# Power.net
KiCad netlist of a schematic drawn in Altium Designer
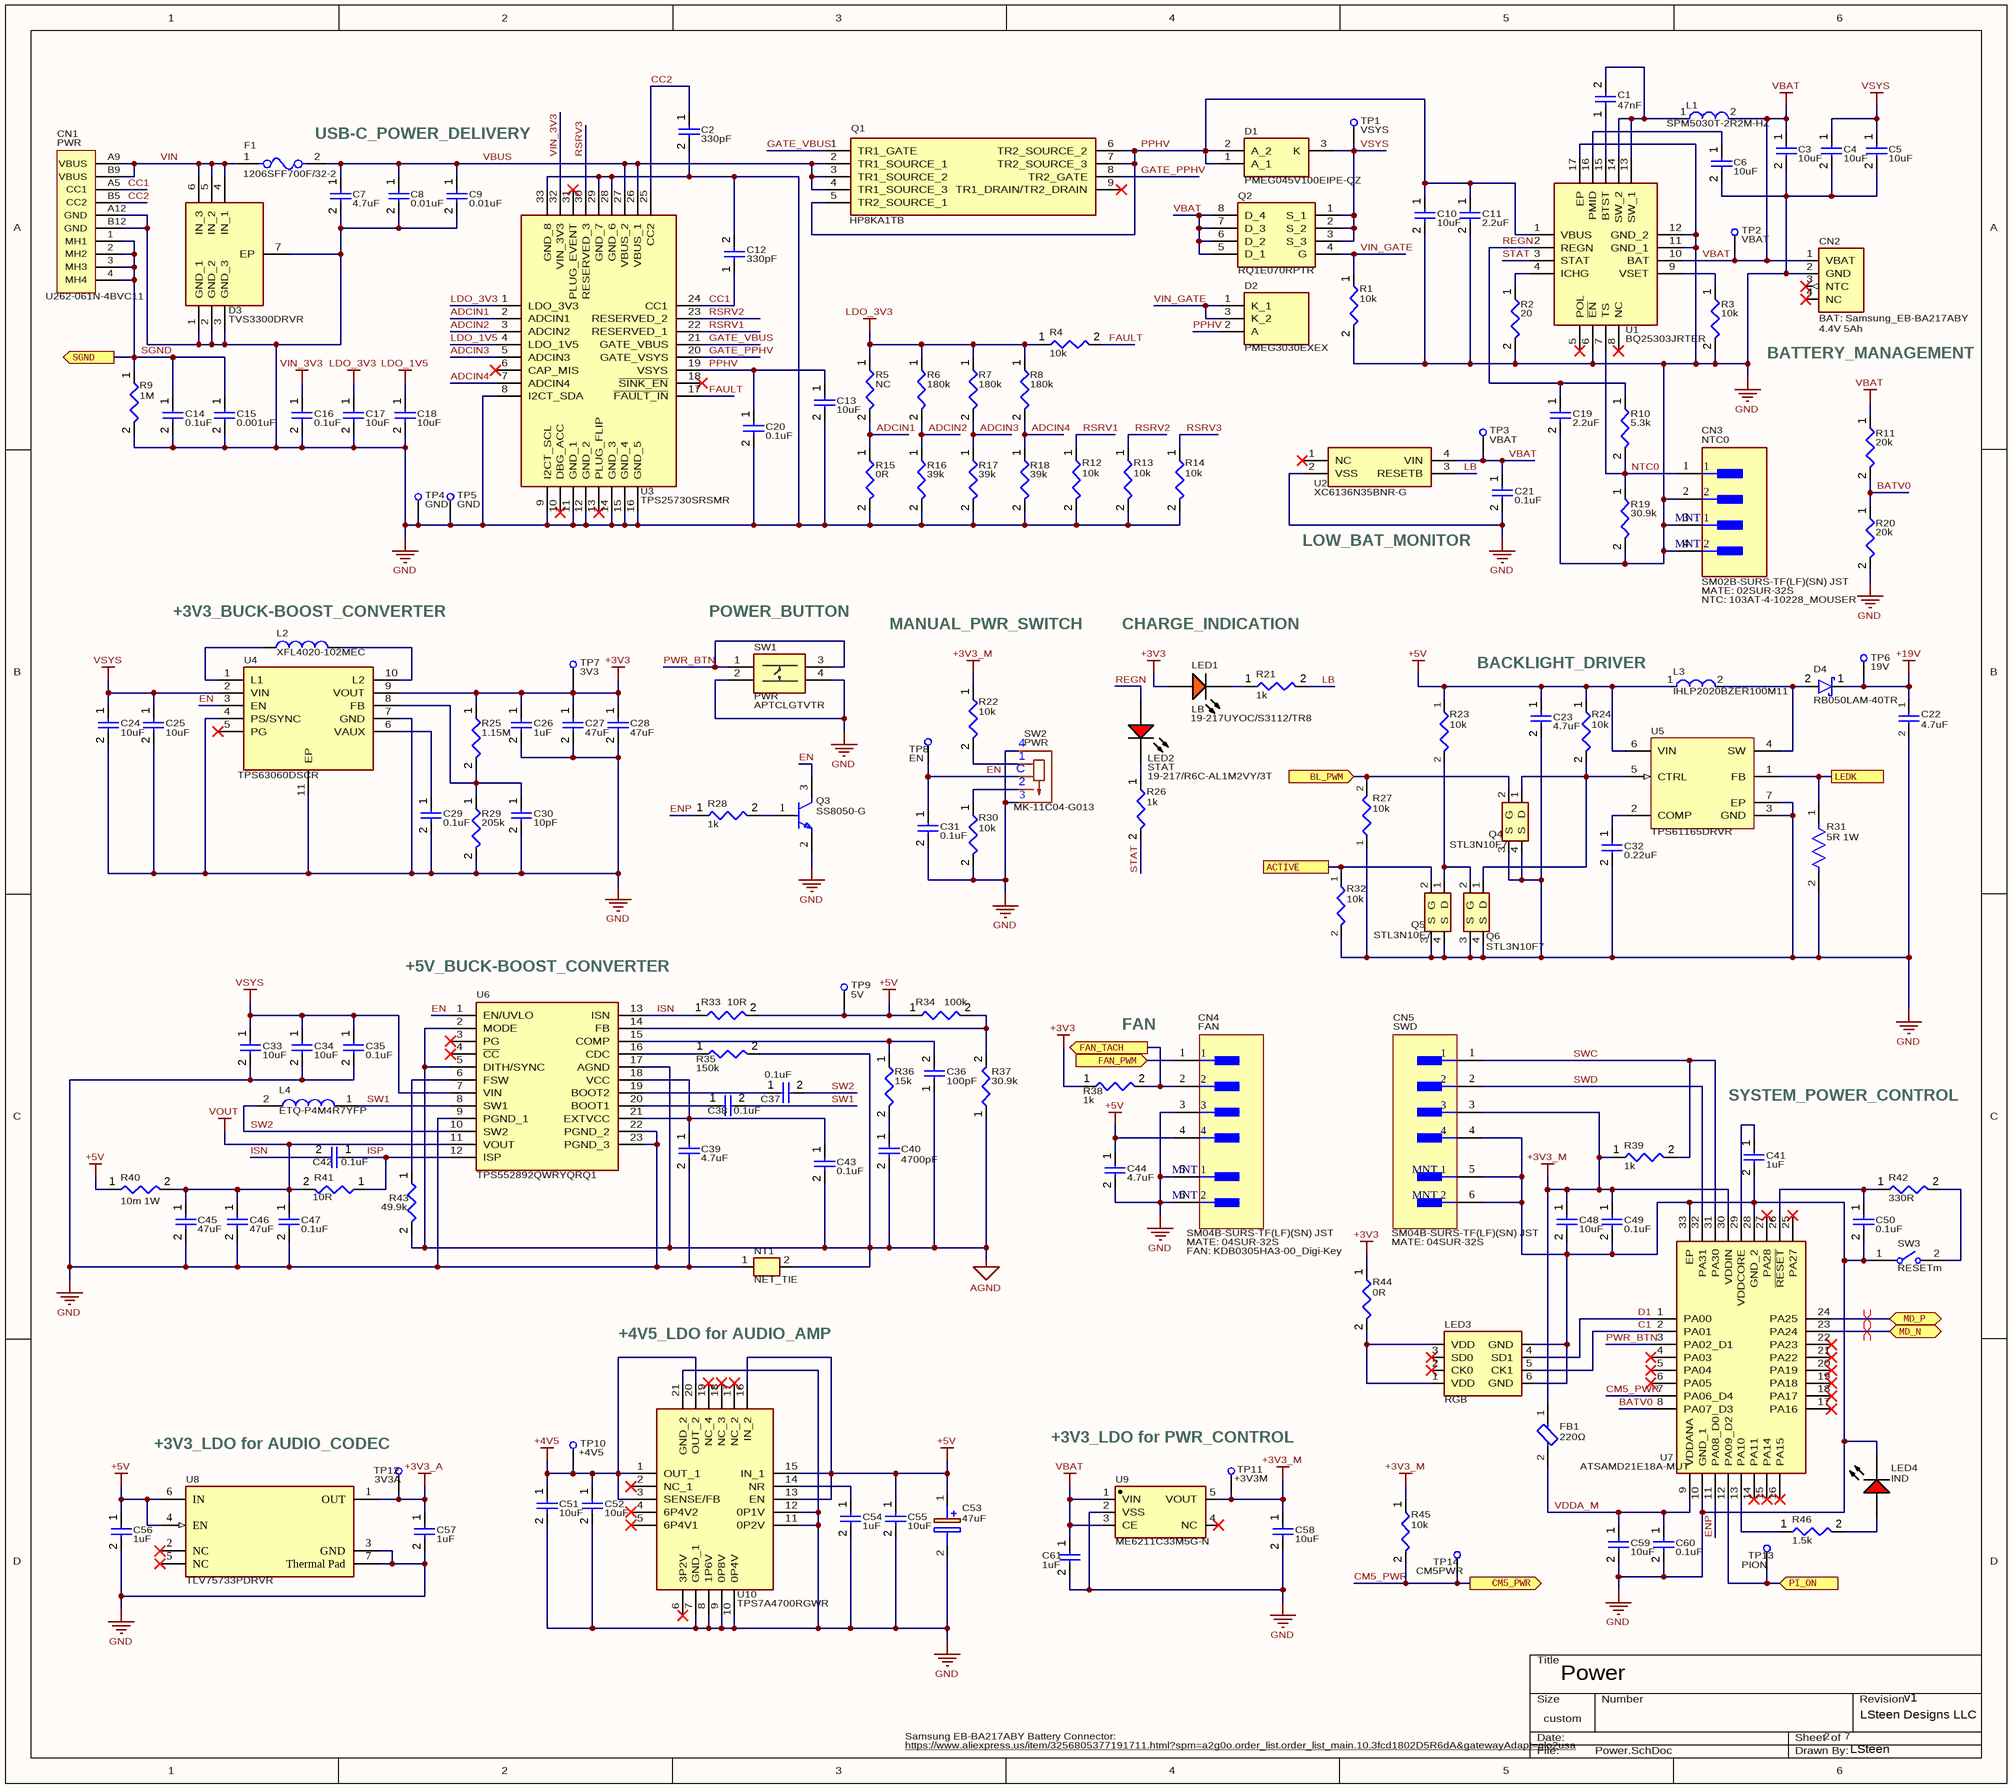
[diagram p0: Power.SchDoc]

(export (version "E")
  (design (tool "Eeschema 10.0.6"))
  (components
    (comp (ref "C1")
      (value "47nF")
      (footprint "CAPC1005X56X25LL10T15")
      (description "Chip Capacitor, 47 nF, +/- 5%, 16 V, 0402 (1005 Metric)")
      (fields (field (name "TOLERANCE") "5%"))
      (libsource (lib "Colorado Technical University") (part "CAP-NP-2"))
    )
    (comp (ref "C2")
      (value "330pF")
      (footprint "CAPC1005X56X25LL10T15")
      (description "Chip Capacitor, 330pF, +/- 5%, 16 V, 0402 (1005 Metric)")
      (fields (field (name "TOLERANCE") "5%"))
      (libsource (lib "Colorado Technical University") (part "CAP-NP-2"))
    )
    (comp (ref "C3")
      (value "10uF")
      (footprint "CAPC0805(2012)145_L")
      (description "Chip Capacitor, 10µF +/-20%, 25V, 0805, Thickness 1.45 mm")
      (fields (field (name "TOLERANCE") "10%"))
      (libsource (lib "Colorado Technical University") (part "CAP-NP-2"))
    )
    (comp (ref "C4")
      (value "10uF")
      (footprint "CAPC0805(2012)145_L")
      (description "Chip Capacitor, 10µF +/-20%, 25V, 0805, Thickness 1.45 mm")
      (fields (field (name "TOLERANCE") "10%"))
      (libsource (lib "Colorado Technical University") (part "CAP-NP-2"))
    )
    (comp (ref "C5")
      (value "10uF")
      (footprint "CAPC0805(2012)145_L")
      (description "Chip Capacitor, 10µF +/-20%, 25V, 0805, Thickness 1.45 mm")
      (fields (field (name "TOLERANCE") "10%"))
      (libsource (lib "Colorado Technical University") (part "CAP-NP-2"))
    )
    (comp (ref "C6")
      (value "10uF")
      (footprint "CAPC0805(2012)145_L")
      (description "Chip Capacitor, 10µF +/-20%, 25V, 0805, Thickness 1.45 mm")
      (fields (field (name "TOLERANCE") "10%"))
      (libsource (lib "Colorado Technical University") (part "CAP-NP-2"))
    )
    (comp (ref "C7")
      (value "4.7uF")
      (footprint "CAPC0603(1608)100_L")
      (description "Chip Capacitor, 4.7uF +/-20%, 10V, 0603, Thickness 1 mm")
      (fields (field (name "TOLERANCE") "10%"))
      (libsource (lib "Colorado Technical University") (part "CAP-NP-2"))
    )
    (comp (ref "C8")
      (value "0.01uF")
      (footprint "CAPC1005X56X25LL10T15")
      (description "Chip Capacitor, 0.01 uF, +/- 5%, 16 V, 0402 (1005 Metric)")
      (fields (field (name "TOLERANCE") "5%"))
      (libsource (lib "Colorado Technical University") (part "CAP-NP-2"))
    )
    (comp (ref "C9")
      (value "0.01uF")
      (footprint "CAPC1005X56X25LL10T15")
      (description "Chip Capacitor, 0.01 uF, +/- 5%, 16 V, 0402 (1005 Metric)")
      (fields (field (name "TOLERANCE") "5%"))
      (libsource (lib "Colorado Technical University") (part "CAP-NP-2"))
    )
    (comp (ref "C10")
      (value "10uF")
      (footprint "CAPC0805(2012)145_L")
      (description "Chip Capacitor, 10µF +/-20%, 25V, 0805, Thickness 1.45 mm")
      (fields (field (name "TOLERANCE") "10%"))
      (libsource (lib "Colorado Technical University") (part "CAP-NP-2"))
    )
    (comp (ref "C11")
      (value "2.2uF")
      (footprint "CAPC0603(1608)100_L")
      (description "Chip Capacitor, 2.2uF +/-20%, 10V, 0603, Thickness 1 mm")
      (fields (field (name "TOLERANCE") "10%"))
      (libsource (lib "Colorado Technical University") (part "CAP-NP-2"))
    )
    (comp (ref "C12")
      (value "330pF")
      (footprint "CAPC1005X56X25LL10T15")
      (description "Chip Capacitor, 330pF, +/- 5%, 16 V, 0402 (1005 Metric)")
      (fields (field (name "TOLERANCE") "5%"))
      (libsource (lib "Colorado Technical University") (part "CAP-NP-2"))
    )
    (comp (ref "C13")
      (value "10uF")
      (footprint "CAPC0603(1608)100_L")
      (description "Chip Capacitor, 10uF +/-20%, 10V, 0603, Thickness 1 mm")
      (fields (field (name "TOLERANCE") "10%"))
      (libsource (lib "Colorado Technical University") (part "CAP-NP-2"))
    )
    (comp (ref "C14")
      (value "0.1uF")
      (footprint "CAPC1005X56X25LL10T15")
      (description "Chip Capacitor, 0.1 uF, +/- 5%, 16 V, 0402 (1005 Metric)")
      (fields (field (name "TOLERANCE") "5%"))
      (libsource (lib "Colorado Technical University") (part "CAP-NP-2"))
    )
    (comp (ref "C15")
      (value "0.001uF")
      (footprint "CAPC1005X56X25LL10T15")
      (description "Chip Capacitor, 0.1 uF, +/- 5%, 16 V, 0402 (1005 Metric)")
      (fields (field (name "TOLERANCE") "5%"))
      (libsource (lib "Colorado Technical University") (part "CAP-NP-2"))
    )
    (comp (ref "C16")
      (value "0.1uF")
      (footprint "CAPC1005X56X25LL10T15")
      (description "Chip Capacitor, 0.1 uF, +/- 5%, 16 V, 0402 (1005 Metric)")
      (fields (field (name "TOLERANCE") "5%"))
      (libsource (lib "Colorado Technical University") (part "CAP-NP-2"))
    )
    (comp (ref "C17")
      (value "10uF")
      (footprint "CAPC0603(1608)100_L")
      (description "Chip Capacitor, 10uF +/-20%, 10V, 0603, Thickness 1 mm")
      (fields (field (name "TOLERANCE") "10%"))
      (libsource (lib "Colorado Technical University") (part "CAP-NP-2"))
    )
    (comp (ref "C18")
      (value "10uF")
      (footprint "CAPC0603(1608)100_L")
      (description "Chip Capacitor, 10uF +/-20%, 10V, 0603, Thickness 1 mm")
      (fields (field (name "TOLERANCE") "10%"))
      (libsource (lib "Colorado Technical University") (part "CAP-NP-2"))
    )
    (comp (ref "C19")
      (value "2.2uF")
      (footprint "CAPC1005X56X25LL10T15")
      (description "Chip Capacitor, 2.2uF uF, +/- 5%, 16 V, 0402 (1005 Metric)")
      (fields (field (name "TOLERANCE") "5%"))
      (libsource (lib "Colorado Technical University") (part "CAP-NP-2"))
    )
    (comp (ref "C20")
      (value "0.1uF")
      (footprint "CAPC1005X56X25LL10T15")
      (description "Chip Capacitor, 0.1 uF, +/- 5%, 16 V, 0402 (1005 Metric)")
      (fields (field (name "TOLERANCE") "5%"))
      (libsource (lib "Colorado Technical University") (part "CAP-NP-2"))
    )
    (comp (ref "C21")
      (value "0.1uF")
      (footprint "CAPC1005X56X25LL10T15")
      (description "Chip Capacitor, 0.1 uF, +/- 5%, 16 V, 0402 (1005 Metric)")
      (fields (field (name "TOLERANCE") "5%"))
      (libsource (lib "Colorado Technical University") (part "CAP-NP-2"))
    )
    (comp (ref "C22")
      (value "4.7uF")
      (footprint "SamacSys:CAPC2012X140N")
      (description "C0805")
      (libsource (lib "SamacSys") (part "C0805"))
    )
    (comp (ref "C23")
      (value "4.7uF")
      (footprint "CAPC0805(2012)145_L")
      (description "Chip Capacitor, 4.7µF +/-20%, 25V, 0805, Thickness 1.45 mm")
      (fields (field (name "TOLERANCE") "10%"))
      (libsource (lib "Colorado Technical University") (part "CAP-NP-2"))
    )
    (comp (ref "C24")
      (value "10uF")
      (footprint "CAPC0603(1608)100_L")
      (description "Chip Capacitor, 10uF +/-20%, 10V, 0603, Thickness 1 mm")
      (fields (field (name "TOLERANCE") "10%"))
      (libsource (lib "Colorado Technical University") (part "CAP-NP-2"))
    )
    (comp (ref "C25")
      (value "10uF")
      (footprint "CAPC0603(1608)100_L")
      (description "Chip Capacitor, 10uF +/-20%, 10V, 0603, Thickness 1 mm")
      (fields (field (name "TOLERANCE") "10%"))
      (libsource (lib "Colorado Technical University") (part "CAP-NP-2"))
    )
    (comp (ref "C26")
      (value "1uF")
      (footprint "CAPC1005X56X25LL10T15")
      (description "Chip Capacitor, 1 uF, +/- 5%, 16 V, 0402 (1005 Metric)")
      (fields (field (name "TOLERANCE") "5%"))
      (libsource (lib "Colorado Technical University") (part "CAP-NP-2"))
    )
    (comp (ref "C27")
      (value "47uF")
      (footprint "CAPC0805(2012)145_L")
      (description "Chip Capacitor, 47µF +/-20%, 25V, 0805, Thickness 1.45 mm")
      (fields (field (name "TOLERANCE") "10%"))
      (libsource (lib "Colorado Technical University") (part "CAP-NP-2"))
    )
    (comp (ref "C28")
      (value "47uF")
      (footprint "CAPC0805(2012)145_L")
      (description "Chip Capacitor, 47µF +/-20%, 25V, 0805, Thickness 1.45 mm")
      (fields (field (name "TOLERANCE") "10%"))
      (libsource (lib "Colorado Technical University") (part "CAP-NP-2"))
    )
    (comp (ref "C29")
      (value "0.1uF")
      (footprint "CAPC1005X56X25LL10T15")
      (description "Chip Capacitor, 0.1 uF, +/- 5%, 16 V, 0402 (1005 Metric)")
      (fields (field (name "TOLERANCE") "5%"))
      (libsource (lib "Colorado Technical University") (part "CAP-NP-2"))
    )
    (comp (ref "C30")
      (value "10pF")
      (footprint "CAPC1005X56X25LL10T15")
      (description "Chip Capacitor, 10 pF, +/- 5%, 16 V, 0402 (1005 Metric)")
      (fields (field (name "TOLERANCE") "5%"))
      (libsource (lib "Colorado Technical University") (part "CAP-NP-2"))
    )
    (comp (ref "C31")
      (value "0.1uF")
      (footprint "CAPC1005X56X25LL10T15")
      (description "Chip Capacitor, 0.1 uF, +/- 5%, 16 V, 0402 (1005 Metric)")
      (fields (field (name "TOLERANCE") "5%"))
      (libsource (lib "Colorado Technical University") (part "CAP-NP-2"))
    )
    (comp (ref "C32")
      (value "0.22uF")
      (footprint "CAPC1005X56X25LL10T15")
      (description "Chip Capacitor, 0.22 uF, +/- 5%, 16 V, 0402 (1005 Metric)")
      (fields (field (name "TOLERANCE") "5%"))
      (libsource (lib "Colorado Technical University") (part "CAP-NP-2"))
    )
    (comp (ref "C33")
      (value "10uF")
      (footprint "CAPC0805(2012)145_L")
      (description "Chip Capacitor, 10µF +/-20%, 25V, 0805, Thickness 1.45 mm")
      (fields (field (name "TOLERANCE") "10%"))
      (libsource (lib "Colorado Technical University") (part "CAP-NP-2"))
    )
    (comp (ref "C34")
      (value "10uF")
      (footprint "CAPC0805(2012)145_L")
      (description "Chip Capacitor, 10µF +/-20%, 25V, 0805, Thickness 1.45 mm")
      (fields (field (name "TOLERANCE") "10%"))
      (libsource (lib "Colorado Technical University") (part "CAP-NP-2"))
    )
    (comp (ref "C35")
      (value "0.1uF")
      (footprint "CAPC1005X56X25LL10T15")
      (description "Chip Capacitor, 0.1 uF, +/- 5%, 16 V, 0402 (1005 Metric)")
      (fields (field (name "TOLERANCE") "5%"))
      (libsource (lib "Colorado Technical University") (part "CAP-NP-2"))
    )
    (comp (ref "C36")
      (value "100pF")
      (footprint "CAPC1005X56X25LL10T15")
      (description "Chip Capacitor, 100 pF, +/- 5%, 16 V, 0402 (1005 Metric)")
      (fields (field (name "TOLERANCE") "5%"))
      (libsource (lib "Colorado Technical University") (part "CAP-NP-2"))
    )
    (comp (ref "C37")
      (value "0.1uF")
      (footprint "CAPC1005X56X25LL10T15")
      (description "Chip Capacitor, 0.1 uF, +/- 5%, 16 V, 0402 (1005 Metric)")
      (fields (field (name "TOLERANCE") "5%"))
      (libsource (lib "Colorado Technical University") (part "CAP-NP-2"))
    )
    (comp (ref "C38")
      (value "0.1uF")
      (footprint "CAPC1005X56X25LL10T15")
      (description "Chip Capacitor, 0.1 uF, +/- 5%, 16 V, 0402 (1005 Metric)")
      (fields (field (name "TOLERANCE") "5%"))
      (libsource (lib "Colorado Technical University") (part "CAP-NP-2"))
    )
    (comp (ref "C39")
      (value "4.7uF")
      (footprint "CAPC0603(1608)100_L")
      (description "Chip Capacitor, 4.7µF +/-20%, 10V, 0603, Thickness 1 mm")
      (fields (field (name "TOLERANCE") "10%"))
      (libsource (lib "Colorado Technical University") (part "CAP-NP-2"))
    )
    (comp (ref "C40")
      (value "4700pF")
      (footprint "CAPC1005X56X25LL10T15")
      (description "Chip Capacitor, 4700 pF, +/- 5%, 16 V, 0402 (1005 Metric)")
      (fields (field (name "TOLERANCE") "5%"))
      (libsource (lib "Colorado Technical University") (part "CAP-NP-2"))
    )
    (comp (ref "C41")
      (value "1uF")
      (footprint "CAPC1005X56X25LL10T15")
      (description "Chip Capacitor, 1 uF, +/- 5%, 16 V, 0402 (1005 Metric)")
      (fields (field (name "TOLERANCE") "5%"))
      (libsource (lib "Colorado Technical University") (part "CAP-NP-2"))
    )
    (comp (ref "C42")
      (value "0.1uF")
      (footprint "CAPC1005X56X25LL10T15")
      (description "Chip Capacitor, 0.1 uF, +/- 5%, 16 V, 0402 (1005 Metric)")
      (fields (field (name "TOLERANCE") "5%"))
      (libsource (lib "Colorado Technical University") (part "CAP-NP-2"))
    )
    (comp (ref "C43")
      (value "0.1uF")
      (footprint "CAPC1005X56X25LL10T15")
      (description "Chip Capacitor, 0.1 uF, +/- 5%, 16 V, 0402 (1005 Metric)")
      (fields (field (name "TOLERANCE") "5%"))
      (libsource (lib "Colorado Technical University") (part "CAP-NP-2"))
    )
    (comp (ref "C44")
      (value "4.7uF")
      (footprint "CAPC0805(2012)145_L")
      (description "Chip Capacitor, 4.7µF +/-20%, 25V, 0805, Thickness 1.45 mm")
      (fields (field (name "TOLERANCE") "10%"))
      (libsource (lib "Colorado Technical University") (part "CAP-NP-2"))
    )
    (comp (ref "C45")
      (value "47uF")
      (footprint "CAPC0805(2012)145_L")
      (description "Chip Capacitor, 47µF +/-40%, 6.3V, 0805, Thickness 1.45 mm")
      (fields (field (name "TOLERANCE") "10%"))
      (libsource (lib "Colorado Technical University") (part "CAP-NP-2"))
    )
    (comp (ref "C46")
      (value "47uF")
      (footprint "CAPC0805(2012)145_L")
      (description "Chip Capacitor, 47µF +/-40%, 6.3V, 0805, Thickness 1.45 mm")
      (fields (field (name "TOLERANCE") "10%"))
      (libsource (lib "Colorado Technical University") (part "CAP-NP-2"))
    )
    (comp (ref "C47")
      (value "0.1uF")
      (footprint "CAPC1005X56X25LL10T15")
      (description "Chip Capacitor, 0.1 uF, +/- 5%, 16 V, 0402 (1005 Metric)")
      (fields (field (name "TOLERANCE") "5%"))
      (libsource (lib "Colorado Technical University") (part "CAP-NP-2"))
    )
    (comp (ref "C48")
      (value "10uF")
      (footprint "CAPC0603(1608)100_L")
      (description "Chip Capacitor, 10uF +/-20%, 10V, 0603, Thickness 1 mm")
      (fields (field (name "TOLERANCE") "10%"))
      (libsource (lib "Colorado Technical University") (part "CAP-NP-2"))
    )
    (comp (ref "C49")
      (value "0.1uF")
      (footprint "CAPC1005X56X25LL10T15")
      (description "Chip Capacitor, 0.1 uF, +/- 5%, 16 V, 0402 (1005 Metric)")
      (fields (field (name "TOLERANCE") "5%"))
      (libsource (lib "Colorado Technical University") (part "CAP-NP-2"))
    )
    (comp (ref "C50")
      (value "0.1uF")
      (footprint "CAPC1005X56X25LL10T15")
      (description "Chip Capacitor, 0.1 uF, +/- 5%, 16 V, 0402 (1005 Metric)")
      (fields (field (name "TOLERANCE") "5%"))
      (libsource (lib "Colorado Technical University") (part "CAP-NP-2"))
    )
    (comp (ref "C51")
      (value "10uF")
      (footprint "CAPC0805(2012)145_L")
      (description "Chip Capacitor, 10µF +/-20%, 25V, 0805, Thickness 1.45 mm")
      (fields (field (name "TOLERANCE") "10%"))
      (libsource (lib "Colorado Technical University") (part "CAP-NP-2"))
    )
    (comp (ref "C52")
      (value "10uF")
      (footprint "CAPC0805(2012)145_L")
      (description "Chip Capacitor, 10µF +/-20%, 25V, 0805, Thickness 1.45 mm")
      (fields (field (name "TOLERANCE") "10%"))
      (libsource (lib "Colorado Technical University") (part "CAP-NP-2"))
    )
    (comp (ref "C53")
      (value "47uF")
      (footprint "SamacSys:CAPPM2014X140N")
      (description "Tantalum TLJR476M010R3200")
      (fields
        (field (name "MANUFACTURER_PART_NUMBER") "TLJR476M010R3200")
        (field (name "MOUSER PART NUMBER") "581-TLJR476M10R3200")
      )
      (libsource (lib "SamacSys") (part "TLJR476M010R3200"))
    )
    (comp (ref "C54")
      (value "1uF")
      (footprint "CAPC0603(1608)100_L")
      (description "Chip Capacitor, 1uF +/-20%, 10V, 0603, Thickness 1 mm")
      (fields (field (name "TOLERANCE") "10%"))
      (libsource (lib "Colorado Technical University") (part "CAP-NP-2"))
    )
    (comp (ref "C55")
      (value "10uF")
      (footprint "CAPC0805(2012)145_L")
      (description "Chip Capacitor, 10µF +/-20%, 25V, 0805, Thickness 1.45 mm")
      (fields (field (name "TOLERANCE") "10%"))
      (libsource (lib "Colorado Technical University") (part "CAP-NP-2"))
    )
    (comp (ref "C56")
      (value "1uF")
      (footprint "CAPC0603(1608)100_L")
      (description "Chip Capacitor, 1uF +/-20%, 10V, 0603, Thickness 1 mm")
      (fields (field (name "TOLERANCE") "10%"))
      (libsource (lib "Colorado Technical University") (part "CAP-NP-2"))
    )
    (comp (ref "C57")
      (value "1uF")
      (footprint "CAPC0603(1608)100_L")
      (description "Chip Capacitor, 1uF +/-20%, 10V, 0603, Thickness 1 mm")
      (fields (field (name "TOLERANCE") "10%"))
      (libsource (lib "Colorado Technical University") (part "CAP-NP-2"))
    )
    (comp (ref "C58")
      (value "10uF")
      (footprint "CAPC0603(1608)100_L")
      (description "Chip Capacitor, 10uF +/-20%, 10V, 0603, Thickness 1 mm")
      (fields (field (name "TOLERANCE") "10%"))
      (libsource (lib "Colorado Technical University") (part "CAP-NP-2"))
    )
    (comp (ref "C59")
      (value "10uF")
      (footprint "CAPC0603(1608)100_L")
      (description "Chip Capacitor, 10uF +/-20%, 10V, 0603, Thickness 1 mm")
      (fields (field (name "TOLERANCE") "10%"))
      (libsource (lib "Colorado Technical University") (part "CAP-NP-2"))
    )
    (comp (ref "C60")
      (value "0.1uF")
      (footprint "CAPC1005X56X25LL10T15")
      (description "Chip Capacitor, 0.1 uF, +/- 5%, 16 V, 0402 (1005 Metric)")
      (fields (field (name "TOLERANCE") "5%"))
      (libsource (lib "Colorado Technical University") (part "CAP-NP-2"))
    )
    (comp (ref "C61")
      (value "1uF")
      (footprint "CAPC0603(1608)100_L")
      (description "Chip Capacitor, 1uF +/-20%, 10V, 0603, Thickness 1 mm")
      (fields (field (name "TOLERANCE") "10%"))
      (libsource (lib "Colorado Technical University") (part "CAP-NP-2"))
    )
    (comp (ref "CN1")
      (value "PWR")
      (footprint "USB-SMD_U262-061N-4BVC11")
      (description "USB-C Connector")
      (fields
        (field (name "MANUFACTURER_PART_NUMBER") "U262-061N-4BVC11")
        (field (name "LCSC PART NUMBER") "C2764612")
      )
      (libsource (lib "Schlib1") (part "U262-061N-4BVC11"))
    )
    (comp (ref "CN2")
      (value "BAT")
      (footprint "BAT_SS_EB-BA217ABY_BRD")
      (description "Samsung battery connector")
      (libsource (lib "Schlib1") (part "BAT_SS_EB-BA217ABY_BRD"))
    )
    (comp (ref "CN3")
      (value "NTC0")
      (footprint "FP-SM02B-SURS-TF_LF_SN-MFG")
      (description "LCSC_CONN HEADER SMD R/A 2POS 0.8MM")
      (libsource (lib "Altium Content Vault") (part "6ebc6fc72a9fd5a6899c7600f385cff"))
    )
    (comp (ref "CN4")
      (value "FAN")
      (footprint "FP-SM04B-SURS-TF_LF_SN-MFG")
      (description "CONN HEADER SMD R/A 4POS 0.8MM")
      (libsource (lib "Altium Content Vault") (part "3b6f738a5616415d78381ad43816e4a"))
    )
    (comp (ref "CN5")
      (value "SWD")
      (footprint "FP-SM04B-SURS-TF_LF_SN-MFG")
      (description "CONN HEADER SMD R/A 4POS 0.8MM")
      (libsource (lib "") (part "3b6f738a5616415d78381ad43816e4a_1"))
    )
    (comp (ref "D1")
      (value "PMEG045V100EIPE-QZ")
      (footprint "SamacSys:PMEG045V100EIPEQZ")
      (description "Schottky Diode")
      (fields (field (name "MOUSER PART NUMBER") "771-MEG045V100EIPEQZ"))
      (libsource (lib "SamacSys") (part "PMEG045V100EIPE-QZ"))
    )
    (comp (ref "D2")
      (value "PMEG3030EXEX")
      (footprint "SamacSys:PMEG4010EXEX")
      (description "Schottky Diode")
      (libsource (lib "SamacSys") (part "PMEG3030EXEX"))
    )
    (comp (ref "D3")
      (value "TVS3300DRVR")
      (footprint "SamacSys:SON65P200X200X80-7N")
      (description "Integrated Circuit")
      (fields (field (name "MOUSER PART NUMBER") "595-TVS3300DRVR"))
      (libsource (lib "SamacSys") (part "TVS3300DRVR"))
    )
    (comp (ref "D4")
      (value "RB050LAM-40TR")
      (footprint "SamacSys:SODFL4725X105N")
      (description "Schottky Diode")
      (fields (field (name "MOUSER PART NUMBER") "755-RB050LAM-40TR"))
      (libsource (lib "SamacSys") (part "RB050LAM-40TR"))
    )
    (comp (ref "F1")
      (value "1206SFF700F/32-2")
      (footprint "FP-1206SFF-MFG")
      (description "FUSE BOARD MOUNT 7A 24VDC 1206")
      (fields
        (field (name "OCTOPART") "https://octopart.com/1206sff700f%2F32-2-littelfuse-74214425")
        (field (name "MANUFACTURER") "Littelfuse")
      )
      (libsource (lib "Altium Content Vault") (part "5bcf9b9f640e542cf0359d10258e979"))
    )
    (comp (ref "FB1")
      (value "220Ω")
      (footprint "FP-BLM18-0_15-t0_5-IPC_B")
      (description "Chip Ferrite Bead, 0603, 220Ω @ 100MHz, 25%, 0.04Ω, 2.5A")
      (libsource (lib "Altium Content Vault") (part "5f30dd21d616792df468990f7003faa"))
    )
    (comp (ref "L1")
      (value "SPM5030T-2R2M-HZ")
      (footprint "FP-SPM5030-MFG")
      (description "FIXED IND 2.2UH 8.5A 21.23 MOHM")
      (fields (field (name "TOLERANCE") "20%"))
      (libsource (lib "Altium Content Vault") (part "725321dda6339637d4d059423bc1c3c"))
    )
    (comp (ref "L2")
      (value "XFL4020-102MEC")
      (footprint "COIL-XFL4020_V")
      (description "Shielded Power Inductor, 1 uH, 64 MHz, -40 to 125 degC, 2-Pin SMD, RoHS, Tape and Reel")
      (fields (field (name "MANUFACTURER") "Coilcraft") (field (name "TOLERANCE") "20%"))
      (libsource (lib "Altium Content Vault") (part "IND-2"))
    )
    (comp (ref "L3")
      (value "IHLP2020BZER100M11")
      (footprint "FP-IHLP-2020BZ-FP_1_905x2-MFG")
      (description "Fixed Inductors Commercial Low DCR Series 10uH 2.2A 182.8mΩ 20%")
      (fields (field (name "TOLERANCE") "20%"))
      (libsource (lib "Altium Content Vault") (part "725321dda6339637d4d059423bc1c3c"))
    )
    (comp (ref "L4")
      (value "ETQ-P4M4R7YFP")
      (footprint "SamacSys:ETQP3M_4M_YFP")
      (description "Inductor")
      (fields (field (name "MOUSER PART NUMBER") "667-ETQ-P4M4R7YFP"))
      (libsource (lib "*") (part "ETQ-P4M4R7YFP"))
    )
    (comp (ref "LED1")
      (value "LB")
      (footprint "LED_0603")
      (fields (field (name "MPN") "19-217UYOC/S3112/TR8"))
      (libsource (lib "SamacSys") (part "19-217UYOC/S3112/TR8"))
    )
    (comp (ref "LED2")
      (value "STAT")
      (footprint "EVRL-0603-2_V")
      (description "Chip LED, Red, 5 V, 25 mA, -40 to 85 degC, 2-Pin SMD (0603), RoHS, Tape and Reel")
      (fields
        (field (name "MANUFACTURER") "Everlight Electronics")
        (field (name "MANUFACTURER PART NUMBER") "19-217/R6C-AL1M2VY/3T")
      )
      (libsource (lib "Altium Content Vault") (part "LED-RED-AK-2"))
    )
    (comp (ref "LED3")
      (value "RGB")
      (footprint "AP102-2020")
      (description "DotStar Micro RGB")
      (fields (field (name "MPN") "AP102-2020"))
      (libsource (lib "Schlib1") (part "AP102-2020"))
    )
    (comp (ref "LED4")
      (value "IND")
      (footprint "EVRL-0603-2_V")
      (description "Chip LED, Red, 5 V, 25 mA, -40 to 85 degC, 2-Pin SMD (0603), RoHS, Tape and Reel")
      (fields
        (field (name "MANUFACTURER") "Everlight Electronics")
        (field (name "MANUFACTURER PART NUMBER") "19-217/R6C-AL1M2VY/3T")
      )
      (libsource (lib "Altium Content Vault") (part "LED-RED-AK-2"))
    )
    (comp (ref "NT1") (value "NET_TIE") (footprint "NET_TIE1") (libsource (lib "Schlib1") (part "NET_TIE")))
    (comp (ref "Q1")
      (value "HP8KA1TB")
      (footprint "SamacSys:HP8KA1TB")
      (description "MOSFET (N-Channel)")
      (fields (field (name "MOUSER PART NUMBER") "755-HP8KA1TB"))
      (libsource (lib "*") (part "HP8KA1TB"))
    )
    (comp (ref "Q2")
      (value "RQ1E070RPTR")
      (footprint "SamacSys:RQ1E070RPTR")
      (description "MOSFET (P-Channel)")
      (fields (field (name "MOUSER PART NUMBER") "755-RQ1E070RPTR"))
      (libsource (lib "SamacSys") (part "RQ1E070RPTR"))
    )
    (comp (ref "Q3")
      (value "SS8050-G")
      (footprint "FP-SS8050-G-MFG")
      (description "NPN TRANSISTOR 1.5A 40V SOT-23 R")
      (libsource (lib "Altium Content Vault") (part "2a1388f82443b098dcd57d24ac7632d"))
    )
    (comp (ref "Q4")
      (value "STL3N10F7")
      (footprint "SamacSys:STL3N10F7")
      (description "MOSFET (N-Channel)")
      (fields (field (name "MOUSER PART NUMBER") "511-STL3N10F7"))
      (libsource (lib "SamacSys") (part "STL3N10F7"))
    )
    (comp (ref "Q5")
      (value "STL3N10F7")
      (footprint "SamacSys:STL3N10F7")
      (description "MOSFET (N-Channel)")
      (fields (field (name "MOUSER PART NUMBER") "511-STL3N10F7"))
      (libsource (lib "SamacSys") (part "STL3N10F7"))
    )
    (comp (ref "Q6")
      (value "STL3N10F7")
      (footprint "SamacSys:STL3N10F7")
      (description "MOSFET (N-Channel)")
      (fields (field (name "MOUSER PART NUMBER") "511-STL3N10F7"))
      (libsource (lib "SamacSys") (part "STL3N10F7"))
    )
    (comp (ref "R1")
      (value "10k")
      (footprint "RESC0402(1005)_L")
      (description "Chip Resistor, 10 kOhms, +/-5 %, 63 mW, -55 to 155 degC, 0402")
      (fields (field (name "TOLERANCE") "5%") (field (name "POWER") "63mW"))
      (libsource (lib "Colorado Technical University") (part "RES-2"))
    )
    (comp (ref "R2")
      (value "20")
      (footprint "RESC0402(1005)_L")
      (description "Chip Resistor, 20 kOhms, +/-5 %, 63 mW, -55 to 155 degC, 0402")
      (fields (field (name "TOLERANCE") "5%") (field (name "POWER") "63mW"))
      (libsource (lib "Colorado Technical University") (part "RES-2"))
    )
    (comp (ref "R3")
      (value "10k")
      (footprint "RESC0402(1005)_L")
      (description "Chip Resistor, 10 kOhms, +/-5 %, 63 mW, -55 to 155 degC, 0402")
      (fields (field (name "TOLERANCE") "5%") (field (name "POWER") "63mW"))
      (libsource (lib "Colorado Technical University") (part "RES-2"))
    )
    (comp (ref "R4")
      (value "10k")
      (footprint "RESC0402(1005)_L")
      (description "Chip Resistor, 10 kOhms, +/-5 %, 63 mW, -55 to 155 degC, 0402")
      (fields (field (name "TOLERANCE") "5%") (field (name "POWER") "63mW"))
      (libsource (lib "Colorado Technical University") (part "RES-2"))
    )
    (comp (ref "R5")
      (value "NC")
      (footprint "RESC0402(1005)_L")
      (description "Chip Resistor, NC, +/-5 %, 63 mW, -55 to 155 degC, 0402")
      (fields (field (name "TOLERANCE") "5%") (field (name "POWER") "63mW"))
      (libsource (lib "Colorado Technical University") (part "RES-2"))
    )
    (comp (ref "R6")
      (value "180k")
      (footprint "RESC0402(1005)_L")
      (description "Chip Resistor, 180 kOhms, +/-5 %, 63 mW, -55 to 155 degC, 0402")
      (fields (field (name "TOLERANCE") "5%") (field (name "POWER") "63mW"))
      (libsource (lib "Colorado Technical University") (part "RES-2"))
    )
    (comp (ref "R7")
      (value "180k")
      (footprint "RESC0402(1005)_L")
      (description "Chip Resistor, 180 kOhms, +/-5 %, 63 mW, -55 to 155 degC, 0402")
      (fields (field (name "TOLERANCE") "5%") (field (name "POWER") "63mW"))
      (libsource (lib "Colorado Technical University") (part "RES-2"))
    )
    (comp (ref "R8")
      (value "180k")
      (footprint "RESC0402(1005)_L")
      (description "Chip Resistor, 180 kOhms, +/-5 %, 63 mW, -55 to 155 degC, 0402")
      (fields (field (name "TOLERANCE") "5%") (field (name "POWER") "63mW"))
      (libsource (lib "Colorado Technical University") (part "RES-2"))
    )
    (comp (ref "R9")
      (value "1M")
      (footprint "RESC0402(1005)_L")
      (description "Chip Resistor, 1 MOhms, +/-5 %, 63 mW, -55 to 155 degC, 0402")
      (fields (field (name "TOLERANCE") "5%") (field (name "POWER") "63mW"))
      (libsource (lib "Colorado Technical University") (part "RES-2"))
    )
    (comp (ref "R10")
      (value "5.3k")
      (footprint "RESC0402(1005)_L")
      (description "Chip Resistor, 5.3 kOhms, +/-5 %, 63 mW, -55 to 155 degC, 0402")
      (fields (field (name "TOLERANCE") "5%") (field (name "POWER") "63mW"))
      (libsource (lib "Colorado Technical University") (part "RES-2"))
    )
    (comp (ref "R11")
      (value "20k")
      (footprint "RESC0402(1005)_L")
      (description "Chip Resistor, 40 kOhms, +/-5 %, 63 mW, -55 to 155 degC, 0402")
      (fields (field (name "TOLERANCE") "5%") (field (name "POWER") "63mW"))
      (libsource (lib "Colorado Technical University") (part "RES-2"))
    )
    (comp (ref "R12")
      (value "10k")
      (footprint "RESC0402(1005)_L")
      (description "Chip Resistor, 10 kOhms, +/-5 %, 63 mW, -55 to 155 degC, 0402")
      (fields (field (name "TOLERANCE") "5%") (field (name "POWER") "63mW"))
      (libsource (lib "Colorado Technical University") (part "RES-2"))
    )
    (comp (ref "R13")
      (value "10k")
      (footprint "RESC0402(1005)_L")
      (description "Chip Resistor, 10 kOhms, +/-5 %, 63 mW, -55 to 155 degC, 0402")
      (fields (field (name "TOLERANCE") "5%") (field (name "POWER") "63mW"))
      (libsource (lib "Colorado Technical University") (part "RES-2"))
    )
    (comp (ref "R14")
      (value "10k")
      (footprint "RESC0402(1005)_L")
      (description "Chip Resistor, 10 kOhms, +/-5 %, 63 mW, -55 to 155 degC, 0402")
      (fields (field (name "TOLERANCE") "5%") (field (name "POWER") "63mW"))
      (libsource (lib "Colorado Technical University") (part "RES-2"))
    )
    (comp (ref "R15")
      (value "0R")
      (footprint "RESC0402(1005)_L")
      (description "Chip Resistor, 0 Ohms, +/-5 %, 63 mW, -55 to 155 degC, 0402")
      (fields (field (name "TOLERANCE") "5%") (field (name "POWER") "63mW"))
      (libsource (lib "Colorado Technical University") (part "RES-2"))
    )
    (comp (ref "R16")
      (value "39k")
      (footprint "RESC0402(1005)_L")
      (description "Chip Resistor, 39 kOhms, +/-5 %, 63 mW, -55 to 155 degC, 0402")
      (fields (field (name "TOLERANCE") "5%") (field (name "POWER") "63mW"))
      (libsource (lib "Colorado Technical University") (part "RES-2"))
    )
    (comp (ref "R17")
      (value "39k")
      (footprint "RESC0402(1005)_L")
      (description "Chip Resistor, 39 kOhms, +/-5 %, 63 mW, -55 to 155 degC, 0402")
      (fields (field (name "TOLERANCE") "5%") (field (name "POWER") "63mW"))
      (libsource (lib "Colorado Technical University") (part "RES-2"))
    )
    (comp (ref "R18")
      (value "39k")
      (footprint "RESC0402(1005)_L")
      (description "Chip Resistor, 39 kOhms, +/-5 %, 63 mW, -55 to 155 degC, 0402")
      (fields (field (name "TOLERANCE") "5%") (field (name "POWER") "63mW"))
      (libsource (lib "Colorado Technical University") (part "RES-2"))
    )
    (comp (ref "R19")
      (value "30.9k")
      (footprint "RESC0402(1005)_L")
      (description "Chip Resistor, 30.9 kOhms, +/-5 %, 63 mW, -55 to 155 degC, 0402")
      (fields (field (name "TOLERANCE") "5%") (field (name "POWER") "63mW"))
      (libsource (lib "Colorado Technical University") (part "RES-2"))
    )
    (comp (ref "R20")
      (value "20k")
      (footprint "RESC0402(1005)_L")
      (description "Chip Resistor, 40 kOhms, +/-5 %, 63 mW, -55 to 155 degC, 0402")
      (fields (field (name "TOLERANCE") "5%") (field (name "POWER") "63mW"))
      (libsource (lib "Colorado Technical University") (part "RES-2"))
    )
    (comp (ref "R21")
      (value "1k")
      (footprint "RESC0402(1005)_L")
      (description "Chip Resistor, 1 kOhms, +/-5 %, 63 mW, -55 to 155 degC, 0402")
      (fields (field (name "TOLERANCE") "5%") (field (name "POWER") "63mW"))
      (libsource (lib "Colorado Technical University") (part "RES-2"))
    )
    (comp (ref "R22")
      (value "10k")
      (footprint "RESC0402(1005)_L")
      (description "Chip Resistor, 10 kOhms, +/-5 %, 63 mW, -55 to 155 degC, 0402")
      (fields (field (name "TOLERANCE") "5%") (field (name "POWER") "63mW"))
      (libsource (lib "Colorado Technical University") (part "RES-2"))
    )
    (comp (ref "R23")
      (value "10k")
      (footprint "SamacSys:ERA2AED122X")
      (description "R0402")
      (libsource (lib "SamacSys") (part "R0402"))
    )
    (comp (ref "R24")
      (value "10k")
      (footprint "RESC0402(1005)_L")
      (description "Chip Resistor, 10 kOhms, +/-5 %, 63 mW, -55 to 155 degC, 0402")
      (fields (field (name "TOLERANCE") "5%") (field (name "POWER") "63mW"))
      (libsource (lib "Colorado Technical University") (part "RES-2"))
    )
    (comp (ref "R25")
      (value "1.15M")
      (footprint "RESC0402(1005)_L")
      (description "Chip Resistor, 1.15 MOhms, +/-5 %, 63 mW, -55 to 155 degC, 0402")
      (fields (field (name "TOLERANCE") "5%") (field (name "POWER") "63mW"))
      (libsource (lib "Colorado Technical University") (part "RES-2"))
    )
    (comp (ref "R26")
      (value "1k")
      (footprint "RESC0402(1005)_L")
      (description "Chip Resistor, 1 kOhms, +/-5 %, 63 mW, -55 to 155 degC, 0402")
      (fields (field (name "TOLERANCE") "5%") (field (name "POWER") "63mW"))
      (libsource (lib "Colorado Technical University") (part "RES-2"))
    )
    (comp (ref "R27")
      (value "10k")
      (footprint "SamacSys:ERA2AED122X")
      (description "R0402")
      (libsource (lib "SamacSys") (part "R0402"))
    )
    (comp (ref "R28")
      (value "1k")
      (footprint "RESC0402(1005)_L")
      (description "Chip Resistor, 1 kOhms, +/-5 %, 63 mW, -55 to 155 degC, 0402")
      (fields (field (name "TOLERANCE") "5%") (field (name "POWER") "63mW"))
      (libsource (lib "Colorado Technical University") (part "RES-2"))
    )
    (comp (ref "R29")
      (value "205k")
      (footprint "RESC0402(1005)_L")
      (description "Chip Resistor, 205 kOhms, +/-5 %, 63 mW, -55 to 155 degC, 0402")
      (fields (field (name "TOLERANCE") "5%") (field (name "POWER") "63mW"))
      (libsource (lib "Colorado Technical University") (part "RES-2"))
    )
    (comp (ref "R30")
      (value "10k")
      (footprint "RESC0402(1005)_L")
      (description "Chip Resistor, 10 kOhms, +/-5 %, 63 mW, -55 to 155 degC, 0402")
      (fields (field (name "TOLERANCE") "5%") (field (name "POWER") "63mW"))
      (libsource (lib "Colorado Technical University") (part "RES-2"))
    )
    (comp (ref "R31")
      (value "5R 1W")
      (footprint "FP-CRCW2512-e3-MFG")
      (description "RES Thick Film, 5.49Ω, 1%, 1W, 100ppm/°C, 2512")
      (fields (field (name "TOLERANCE") "1%") (field (name "MPN") "HoAR2512-1W-5R-0.1%-TCR25"))
      (libsource (lib "Altium Content Vault") (part "1029c3af85768c4190bb7ad29bc67b5"))
    )
    (comp (ref "R32")
      (value "10k")
      (footprint "SamacSys:ERA2AED122X")
      (description "R0402")
      (libsource (lib "SamacSys") (part "R0402"))
    )
    (comp (ref "R33")
      (value "10R")
      (footprint "RESC0402(1005)_L")
      (description "Chip Resistor, 10 Ohms, +/-5 %, 63 mW, -55 to 155 degC, 0402")
      (fields (field (name "TOLERANCE") "5%") (field (name "POWER") "63mW"))
      (libsource (lib "Colorado Technical University") (part "RES-2"))
    )
    (comp (ref "R34")
      (value "100k")
      (footprint "RESC0402(1005)_L")
      (description "Chip Resistor, 100 kOhms, +/-5 %, 63 mW, -55 to 155 degC, 0402")
      (fields (field (name "TOLERANCE") "5%") (field (name "POWER") "63mW"))
      (libsource (lib "Colorado Technical University") (part "RES-2"))
    )
    (comp (ref "R35")
      (value "150k")
      (footprint "RESC0402(1005)_L")
      (description "Chip Resistor, 150 kOhms, +/-5 %, 63 mW, -55 to 155 degC, 0402")
      (fields (field (name "TOLERANCE") "5%") (field (name "POWER") "63mW"))
      (libsource (lib "Colorado Technical University") (part "RES-2"))
    )
    (comp (ref "R36")
      (value "15k")
      (footprint "RESC0402(1005)_L")
      (description "Chip Resistor, 15 kOhms, +/-5 %, 63 mW, -55 to 155 degC, 0402")
      (fields (field (name "TOLERANCE") "5%") (field (name "POWER") "63mW"))
      (libsource (lib "Colorado Technical University") (part "RES-2"))
    )
    (comp (ref "R37")
      (value "30.9k")
      (footprint "RESC0402(1005)_L")
      (description "Chip Resistor, 30.9 kOhms, +/-5 %, 63 mW, -55 to 155 degC, 0402")
      (fields (field (name "TOLERANCE") "5%") (field (name "POWER") "63mW"))
      (libsource (lib "Colorado Technical University") (part "RES-2"))
    )
    (comp (ref "R38")
      (value "1k")
      (footprint "RESC0402(1005)_L")
      (description "Chip Resistor, 1 kOhms, +/-5 %, 63 mW, -55 to 155 degC, 0402")
      (fields (field (name "TOLERANCE") "5%") (field (name "POWER") "63mW"))
      (libsource (lib "Colorado Technical University") (part "RES-2"))
    )
    (comp (ref "R39")
      (value "1k")
      (footprint "RESC0402(1005)_L")
      (description "Chip Resistor, 1 kOhms, +/-5 %, 63 mW, -55 to 155 degC, 0402")
      (fields (field (name "TOLERANCE") "5%") (field (name "POWER") "63mW"))
      (libsource (lib "Colorado Technical University") (part "RES-2"))
    )
    (comp (ref "R40")
      (value "10m 1W")
      (footprint "RESC3216X60X45ML15T20")
      (description "Chip Resistor, 10 mOhm, +/- 1%, 0.25 W, -55 to 155 degC, 1206 (3216 Metric)")
      (fields (field (name "TOLERANCE") "1%") (field (name "POWER") "1W"))
      (libsource (lib "Colorado Technical University") (part "RES-2"))
    )
    (comp (ref "R41")
      (value "10R")
      (footprint "RESC0402(1005)_L")
      (description "Chip Resistor, 10 Ohms, +/-5 %, 63 mW, -55 to 155 degC, 0402")
      (fields (field (name "TOLERANCE") "5%") (field (name "POWER") "63mW"))
      (libsource (lib "Colorado Technical University") (part "RES-2"))
    )
    (comp (ref "R42")
      (value "330R")
      (footprint "RESC0402(1005)_L")
      (description "Chip Resistor, 330 Ohms, +/-5 %, 63 mW, -55 to 155 degC, 0402")
      (fields (field (name "TOLERANCE") "5%") (field (name "POWER") "63mW"))
      (libsource (lib "Colorado Technical University") (part "RES-2"))
    )
    (comp (ref "R43")
      (value "49.9k")
      (footprint "RESC0402(1005)_L")
      (description "Chip Resistor, 49.9 kOhms, +/-5 %, 63 mW, -55 to 155 degC, 0402")
      (fields (field (name "TOLERANCE") "5%") (field (name "POWER") "63mW"))
      (libsource (lib "Colorado Technical University") (part "RES-2"))
    )
    (comp (ref "R44")
      (value "0R")
      (footprint "RESC0402(1005)_L")
      (description "Chip Resistor, 0 Ohms, +/-5 %, 63 mW, -55 to 155 degC, 0402")
      (fields (field (name "TOLERANCE") "5%") (field (name "POWER") "63mW"))
      (libsource (lib "Colorado Technical University") (part "RES-2"))
    )
    (comp (ref "R45")
      (value "10k")
      (footprint "RESC0402(1005)_L")
      (description "Chip Resistor, 10 kOhms, +/-5 %, 63 mW, -55 to 155 degC, 0402")
      (fields (field (name "TOLERANCE") "5%") (field (name "POWER") "63mW"))
      (libsource (lib "Colorado Technical University") (part "RES-2"))
    )
    (comp (ref "R46")
      (value "1.5k")
      (footprint "RESC0402(1005)_L")
      (description "Chip Resistor, 1.5 kOhms, +/-5 %, 63 mW, -55 to 155 degC, 0402")
      (fields (field (name "TOLERANCE") "5%") (field (name "POWER") "63mW"))
      (libsource (lib "Colorado Technical University") (part "RES-2"))
    )
    (comp (ref "SW1")
      (value "PWR")
      (footprint "SamacSys:APTCLGTVTR")
      (description "Switch")
      (fields
        (field (name "MANUFACTURER_PART_NUMBER") "APTCLGTVTR")
        (field (name "MOUSER PART NUMBER") "642-APTCLGTVTR")
      )
      (libsource (lib "SamacSys") (part "APTCLGTVTR"))
    )
    (comp (ref "SW2")
      (value "PWR")
      (footprint "SW-SMD_MK-11C04-G013")
      (description "SPDT 1A 6V Slide Switch")
      (libsource (lib "Schlib1") (part "MK-11C04-G013"))
    )
    (comp (ref "SW3")
      (value "RESETm")
      (footprint "FP-B3U-1000P-MFG")
      (description "LCSC SWITCH TACTILE SPST-NO 0.05A 12V")
      (libsource (lib "Altium Content Vault") (part "ae622034201233ca1abcedc05908f33"))
    )
    (comp (ref "TP1")
      (value "VSYS")
      (footprint "TP")
      (description "TestPoint")
      (libsource (lib "Schlib1") (part "TestPoint"))
    )
    (comp (ref "TP2")
      (value "VBAT")
      (footprint "TP")
      (description "TestPoint")
      (libsource (lib "Schlib1") (part "TestPoint"))
    )
    (comp (ref "TP3")
      (value "VBAT")
      (footprint "TP")
      (description "TestPoint")
      (libsource (lib "Schlib1") (part "TestPoint"))
    )
    (comp (ref "TP4")
      (value "GND")
      (footprint "TP")
      (description "TestPoint")
      (libsource (lib "Schlib1") (part "TestPoint"))
    )
    (comp (ref "TP5")
      (value "GND")
      (footprint "TP")
      (description "TestPoint")
      (libsource (lib "Schlib1") (part "TestPoint"))
    )
    (comp (ref "TP6")
      (value "19V")
      (footprint "TP")
      (description "TestPoint")
      (libsource (lib "Schlib1") (part "TestPoint"))
    )
    (comp (ref "TP7")
      (value "3V3")
      (footprint "TP")
      (description "TestPoint")
      (libsource (lib "Schlib1") (part "TestPoint"))
    )
    (comp (ref "TP8")
      (value "EN")
      (footprint "TP")
      (description "TestPoint")
      (libsource (lib "Schlib1") (part "TestPoint"))
    )
    (comp (ref "TP9")
      (value "5V")
      (footprint "TP")
      (description "TestPoint")
      (libsource (lib "Schlib1") (part "TestPoint"))
    )
    (comp (ref "TP10")
      (value "+4V5")
      (footprint "TP")
      (description "TestPoint")
      (libsource (lib "Schlib1") (part "TestPoint"))
    )
    (comp (ref "TP11")
      (value "+3V3M")
      (footprint "TP")
      (description "TestPoint")
      (libsource (lib "Schlib1") (part "TestPoint"))
    )
    (comp (ref "TP12")
      (value "3V3A")
      (footprint "TP")
      (description "TestPoint")
      (libsource (lib "Schlib1") (part "TestPoint"))
    )
    (comp (ref "TP13")
      (value "PION")
      (footprint "TP")
      (description "TestPoint")
      (libsource (lib "Schlib1") (part "TestPoint"))
    )
    (comp (ref "TP14")
      (value "CM5PWR")
      (footprint "TP")
      (description "TestPoint")
      (libsource (lib "Schlib1") (part "TestPoint"))
    )
    (comp (ref "U1")
      (value "BQ25303JRTER")
      (footprint "SamacSys:QFN50P300X300X80-17N-D")
      (description "Integrated Circuit")
      (fields (field (name "MOUSER PART NUMBER") "595-BQ25303JRTER"))
      (libsource (lib "*") (part "BQ25303JRTER"))
    )
    (comp (ref "U2")
      (value "XC6136N35BNR-G")
      (footprint "SamacSys:XC6136C12ANRG")
      (description "Integrated Circuit")
      (fields (field (name "MOUSER PART NUMBER") "865-XC6136N35BNR-G"))
      (libsource (lib "SamacSys") (part "XC6136N35BNR-G"))
    )
    (comp (ref "U3")
      (value "TPS25730SRSMR")
      (footprint "QFN40P400X400X100-33N-D")
      (description "Integrated Circuit")
      (fields (field (name "MOUSER PART NUMBER") "595-TPS25730SRSMR"))
      (libsource (lib "SamacSys") (part "TPS25730SRSMR"))
    )
    (comp (ref "U4")
      (value "TPS63060DSCR")
      (footprint "SamacSys:SON50P300X300X80-11N-D")
      (description "Integrated Circuit")
      (fields (field (name "MOUSER PART NUMBER") "595-TPS63060DSCR"))
      (libsource (lib "SamacSys") (part "TPS63060DSCR"))
    )
    (comp (ref "U5")
      (value "TPS61165DRVR")
      (footprint "DRV0006A_V")
      (fields (field (name "MANUFACTURER") "Texas Instruments"))
      (libsource (lib "Altium Content Vault") (part "TI-TPS6116XDRV6-1600X1000TP"))
    )
    (comp (ref "U6")
      (value "TPS552892QWRYQRQ1")
      (footprint "SamacSys:TPS552892QWRYQRQ1")
      (description "Integrated Circuit")
      (fields (field (name "MOUSER PART NUMBER") "595-PS552892QWRYQRQ1"))
      (libsource (lib "*") (part "TPS552892QWRYQRQ1"))
    )
    (comp (ref "U7")
      (value "ATSAMD21E18A-MUT")
      (footprint "SamacSys:QFN50P500X500X90-33N-D")
      (description "Integrated Circuit")
      (fields (field (name "MOUSER PART NUMBER") "556-ATSAMD21E18A-MUT"))
      (libsource (lib "SamacSys") (part "ATSAMD21E18A-MUT"))
    )
    (comp (ref "U8")
      (value "TLV75733PDRVR")
      (footprint "FP-DRV0006A-IPC_B")
      (description "IC REG LINEAR 3.3V 1A 6WSON")
      (libsource (lib "Altium Content Vault") (part "0b05c65f2e02c79b80966f21e07e3b1"))
    )
    (comp (ref "U9")
      (value "ME6211C33M5G-N")
      (footprint "SOT95P270X145-5N")
      (description "LCSC +3.3V LDO 500mA VDIF=120mV@100mA")
      (libsource (lib "Schlib1") (part "ME6211C33M5G-N"))
    )
    (comp (ref "U10")
      (value "TPS7A4700RGWR")
      (footprint "SamacSys:QFN65P500X500X100-21N-D")
      (description "Integrated Circuit")
      (fields (field (name "MOUSER PART NUMBER") "595-TPS7A4700RGWR"))
      (libsource (lib "SamacSys") (part "TPS7A4700RGWR"))
    )
  )
  (nets
    (net (code "1") (name "+3V3") (class "Default")
      (node (ref "C26") (pin "1") (pinfunction "1_1") (pintype "passive"))
      (node (ref "C27") (pin "1") (pinfunction "1_1") (pintype "passive"))
      (node (ref "C28") (pin "1") (pinfunction "1_1") (pintype "passive"))
      (node (ref "LED1") (pin "1") (pinfunction "A_1") (pintype "passive"))
      (node (ref "R25") (pin "1") (pinfunction "1_1") (pintype "passive"))
      (node (ref "R38") (pin "1") (pinfunction "1_1") (pintype "passive"))
      (node (ref "R44") (pin "1") (pinfunction "1_1") (pintype "passive"))
      (node (ref "TP7") (pin "1") (pinfunction "1_1") (pintype "passive"))
      (node (ref "U4") (pin "9") (pinfunction "VOUT_9") (pintype "passive"))
    )
    (net (code "2") (name "+3V3_A") (class "Default")
      (node (ref "C57") (pin "1") (pinfunction "1_1") (pintype "passive"))
      (node (ref "TP12") (pin "1") (pinfunction "1_1") (pintype "passive"))
      (node (ref "U8") (pin "1") (pinfunction "OUT_1") (pintype "power_in"))
    )
    (net (code "3") (name "+3V3_M") (class "Default")
      (node (ref "C48") (pin "1") (pinfunction "1_1") (pintype "passive"))
      (node (ref "C49") (pin "1") (pinfunction "1_1") (pintype "passive"))
      (node (ref "C58") (pin "1") (pinfunction "1_1") (pintype "passive"))
      (node (ref "CN5") (pin "3") (pinfunction "3_3") (pintype "passive"))
      (node (ref "FB1") (pin "1") (pinfunction "1_1") (pintype "passive"))
      (node (ref "R22") (pin "1") (pinfunction "1_1") (pintype "passive"))
      (node (ref "R39") (pin "1") (pinfunction "1_1") (pintype "passive"))
      (node (ref "R45") (pin "1") (pinfunction "1_1") (pintype "passive"))
      (node (ref "TP11") (pin "1") (pinfunction "1_1") (pintype "passive"))
      (node (ref "U7") (pin "30") (pinfunction "VDDIN_30") (pintype "passive"))
      (node (ref "U9") (pin "5") (pinfunction "VOUT_5") (pintype "passive"))
    )
    (net (code "4") (name "+4V5") (class "Default")
      (node (ref "C51") (pin "1") (pinfunction "1_1") (pintype "passive"))
      (node (ref "C52") (pin "1") (pinfunction "1_1") (pintype "passive"))
      (node (ref "TP10") (pin "1") (pinfunction "1_1") (pintype "passive"))
      (node (ref "U10") (pin "1") (pinfunction "OUT_1_1") (pintype "passive"))
      (node (ref "U10") (pin "20") (pinfunction "OUT_2_20") (pintype "passive"))
      (node (ref "U10") (pin "3") (pinfunction "SENSE/FB_3") (pintype "passive"))
    )
    (net (code "5") (name "+5V") (class "Default")
      (node (ref "C23") (pin "1") (pinfunction "1_1") (pintype "passive"))
      (node (ref "C44") (pin "1") (pinfunction "1_1") (pintype "passive"))
      (node (ref "C53") (pin "1") (pinfunction "+_1") (pintype "passive"))
      (node (ref "C55") (pin "1") (pinfunction "1_1") (pintype "passive"))
      (node (ref "C56") (pin "1") (pinfunction "1_1") (pintype "passive"))
      (node (ref "CN4") (pin "4") (pinfunction "4_4") (pintype "passive"))
      (node (ref "L3") (pin "1") (pinfunction "1_1") (pintype "passive"))
      (node (ref "R23") (pin "1") (pinfunction "1_1") (pintype "passive"))
      (node (ref "R24") (pin "1") (pinfunction "1_1") (pintype "passive"))
      (node (ref "R33") (pin "2") (pinfunction "2_2") (pintype "passive"))
      (node (ref "R34") (pin "1") (pinfunction "1_1") (pintype "passive"))
      (node (ref "R40") (pin "1") (pinfunction "1_1") (pintype "passive"))
      (node (ref "TP9") (pin "1") (pinfunction "1_1") (pintype "passive"))
      (node (ref "U10") (pin "13") (pinfunction "EN_13") (pintype "passive"))
      (node (ref "U10") (pin "15") (pinfunction "IN_1_15") (pintype "passive"))
      (node (ref "U10") (pin "16") (pinfunction "IN_2_16") (pintype "passive"))
      (node (ref "U5") (pin "6") (pinfunction "VIN_6") (pintype "power_in"))
      (node (ref "U8") (pin "4") (pinfunction "EN_4") (pintype "input"))
      (node (ref "U8") (pin "6") (pinfunction "IN_6") (pintype "power_in"))
    )
    (net (code "6") (name "+19V") (class "Default")
      (node (ref "C22") (pin "1") (pinfunction "1_1") (pintype "passive"))
      (node (ref "D4") (pin "1") (pinfunction "1_1") (pintype "passive"))
      (node (ref "TP6") (pin "1") (pinfunction "1_1") (pintype "passive"))
    )
    (net (code "7") (name "/ACTIVE") (class "Default")
      (node (ref "Q5") (pin "2") (pinfunction "G_2") (pintype "passive"))
      (node (ref "R32") (pin "1") (pinfunction "1_1") (pintype "passive"))
    )
    (net (code "8") (name "/ADCIN1") (class "Default")
      (node (ref "R15") (pin "1") (pinfunction "1_1") (pintype "passive"))
      (node (ref "R5") (pin "2") (pinfunction "2_2") (pintype "passive"))
      (node (ref "U3") (pin "2") (pinfunction "ADCIN1_2") (pintype "passive"))
    )
    (net (code "9") (name "/ADCIN2") (class "Default")
      (node (ref "R16") (pin "1") (pinfunction "1_1") (pintype "passive"))
      (node (ref "R6") (pin "2") (pinfunction "2_2") (pintype "passive"))
      (node (ref "U3") (pin "3") (pinfunction "ADCIN2_3") (pintype "passive"))
    )
    (net (code "10") (name "/ADCIN3") (class "Default")
      (node (ref "R17") (pin "1") (pinfunction "1_1") (pintype "passive"))
      (node (ref "R7") (pin "2") (pinfunction "2_2") (pintype "passive"))
      (node (ref "U3") (pin "5") (pinfunction "ADCIN3_5") (pintype "passive"))
    )
    (net (code "11") (name "/ADCIN4") (class "Default")
      (node (ref "R18") (pin "1") (pinfunction "1_1") (pintype "passive"))
      (node (ref "R8") (pin "2") (pinfunction "2_2") (pintype "passive"))
      (node (ref "U3") (pin "7") (pinfunction "ADCIN4_7") (pintype "passive"))
    )
    (net (code "12") (name "/BATV0") (class "Default")
      (node (ref "R11") (pin "2") (pinfunction "2_2") (pintype "passive"))
      (node (ref "R20") (pin "1") (pinfunction "1_1") (pintype "passive"))
      (node (ref "U7") (pin "8") (pinfunction "PA07_D3_8") (pintype "passive"))
    )
    (net (code "13") (name "/BL_PWM") (class "Default")
      (node (ref "Q4") (pin "2") (pinfunction "G_2") (pintype "passive"))
      (node (ref "R27") (pin "2") (pinfunction "2_2") (pintype "passive"))
    )
    (net (code "14") (name "/C1") (class "Default")
      (node (ref "LED3") (pin "5") (pinfunction "CK1_5") (pintype "passive"))
      (node (ref "U7") (pin "2") (pinfunction "PA01_2") (pintype "passive"))
    )
    (net (code "15") (name "/CC1") (class "Default")
      (node (ref "C12") (pin "1") (pinfunction "1_1") (pintype "passive"))
      (node (ref "CN1") (pin "A5") (pinfunction "CC1_A5") (pintype "passive"))
      (node (ref "U3") (pin "24") (pinfunction "CC1_24") (pintype "passive"))
    )
    (net (code "16") (name "/CC2") (class "Default")
      (node (ref "C2") (pin "1") (pinfunction "1_1") (pintype "passive"))
      (node (ref "CN1") (pin "B5") (pinfunction "CC2_B5") (pintype "passive"))
      (node (ref "U3") (pin "25") (pinfunction "CC2_25") (pintype "passive"))
    )
    (net (code "17") (name "/CM5_PWR") (class "Default")
      (node (ref "R45") (pin "2") (pinfunction "2_2") (pintype "passive"))
      (node (ref "TP14") (pin "1") (pinfunction "1_1") (pintype "passive"))
      (node (ref "U7") (pin "7") (pinfunction "PA06_D4_7") (pintype "passive"))
    )
    (net (code "18") (name "/D1") (class "Default")
      (node (ref "LED3") (pin "4") (pinfunction "SD1_4") (pintype "passive"))
      (node (ref "U7") (pin "1") (pinfunction "PA00_1") (pintype "passive"))
    )
    (net (code "19") (name "/EN") (class "Default")
      (node (ref "C31") (pin "1") (pinfunction "1_1") (pintype "passive"))
      (node (ref "Q3") (pin "3") (pinfunction "C_3") (pintype "passive"))
      (node (ref "SW2") (pin "C") (pinfunction "C_C") (pintype "power_in"))
      (node (ref "TP8") (pin "1") (pinfunction "1_1") (pintype "passive"))
      (node (ref "U4") (pin "3") (pinfunction "EN_3") (pintype "passive"))
      (node (ref "U6") (pin "1") (pinfunction "EN/UVLO_1") (pintype "passive"))
    )
    (net (code "20") (name "/ENP") (class "Default")
      (node (ref "R28") (pin "1") (pinfunction "1_1") (pintype "passive"))
      (node (ref "U7") (pin "11") (pinfunction "PA08_D0_11") (pintype "passive"))
    )
    (net (code "21") (name "/FAN_PWM") (class "Default")
      (node (ref "CN4") (pin "1") (pinfunction "1_1") (pintype "passive"))
    )
    (net (code "22") (name "/FAN_TACH") (class "Default")
      (node (ref "CN4") (pin "2") (pinfunction "2_2") (pintype "passive"))
      (node (ref "R38") (pin "2") (pinfunction "2_2") (pintype "passive"))
    )
    (net (code "23") (name "/FAULT") (class "Default")
      (node (ref "R4") (pin "2") (pinfunction "2_2") (pintype "passive"))
      (node (ref "U3") (pin "17") (pinfunction "~{FAULT_IN}_17") (pintype "passive"))
    )
    (net (code "24") (name "/GATE_PPHV") (class "Default")
      (node (ref "Q1") (pin "8") (pinfunction "TR2_GATE_8") (pintype "passive"))
      (node (ref "U3") (pin "20") (pinfunction "GATE_VSYS_20") (pintype "passive"))
    )
    (net (code "25") (name "/GATE_VBUS") (class "Default")
      (node (ref "Q1") (pin "1") (pinfunction "TR1_GATE_1") (pintype "passive"))
      (node (ref "U3") (pin "21") (pinfunction "GATE_VBUS_21") (pintype "passive"))
    )
    (net (code "26") (name "/ISN") (class "Default")
      (node (ref "C42") (pin "2") (pinfunction "2_2") (pintype "passive"))
      (node (ref "R33") (pin "1") (pinfunction "1_1") (pintype "passive"))
      (node (ref "U6") (pin "13") (pinfunction "ISN_13") (pintype "passive"))
    )
    (net (code "27") (name "/ISP") (class "Default")
      (node (ref "C42") (pin "1") (pinfunction "1_1") (pintype "passive"))
      (node (ref "R41") (pin "1") (pinfunction "1_1") (pintype "passive"))
      (node (ref "U6") (pin "12") (pinfunction "ISP_12") (pintype "passive"))
    )
    (net (code "28") (name "/LB") (class "Default")
      (node (ref "R21") (pin "2") (pinfunction "2_2") (pintype "passive"))
      (node (ref "U2") (pin "3") (pinfunction "RESETB_3") (pintype "passive"))
    )
    (net (code "29") (name "/LEDK") (class "Default")
      (node (ref "R31") (pin "1") (pinfunction "1_1") (pintype "passive"))
      (node (ref "U5") (pin "1") (pinfunction "FB_1") (pintype "passive"))
    )
    (net (code "30") (name "/MD_N") (class "Default")
      (node (ref "U7") (pin "23") (pinfunction "PA24_23") (pintype "passive"))
    )
    (net (code "31") (name "/MD_P") (class "Default")
      (node (ref "U7") (pin "24") (pinfunction "PA25_24") (pintype "passive"))
    )
    (net (code "32") (name "/NTC0") (class "Default")
      (node (ref "CN3") (pin "1") (pinfunction "1_1") (pintype "passive"))
      (node (ref "R10") (pin "2") (pinfunction "2_2") (pintype "passive"))
      (node (ref "R19") (pin "1") (pinfunction "1_1") (pintype "passive"))
      (node (ref "U1") (pin "7") (pinfunction "TS_7") (pintype "passive"))
    )
    (net (code "33") (name "/PI_ON") (class "Default")
      (node (ref "TP13") (pin "1") (pinfunction "1_1") (pintype "passive"))
      (node (ref "U7") (pin "12") (pinfunction "PA09_D2_12") (pintype "passive"))
    )
    (net (code "34") (name "/PPHV") (class "Default")
      (node (ref "C10") (pin "1") (pinfunction "1_1") (pintype "passive"))
      (node (ref "C11") (pin "1") (pinfunction "1_1") (pintype "passive"))
      (node (ref "C13") (pin "1") (pinfunction "1_1") (pintype "passive"))
      (node (ref "C20") (pin "1") (pinfunction "1_1") (pintype "passive"))
      (node (ref "D1") (pin "1") (pinfunction "A_1_1") (pintype "passive"))
      (node (ref "D1") (pin "2") (pinfunction "A_2_2") (pintype "passive"))
      (node (ref "D2") (pin "2") (pinfunction "A_2") (pintype "passive"))
      (node (ref "Q1") (pin "5") (pinfunction "TR2_SOURCE_1_5") (pintype "passive"))
      (node (ref "Q1") (pin "6") (pinfunction "TR2_SOURCE_2_6") (pintype "passive"))
      (node (ref "Q1") (pin "7") (pinfunction "TR2_SOURCE_3_7") (pintype "passive"))
      (node (ref "U1") (pin "1") (pinfunction "VBUS_1") (pintype "passive"))
      (node (ref "U3") (pin "19") (pinfunction "VSYS_19") (pintype "passive"))
    )
    (net (code "35") (name "/PWR_BTN") (class "Default")
      (node (ref "SW1") (pin "1") (pinfunction "1_1") (pintype "passive"))
      (node (ref "SW1") (pin "3") (pinfunction "3_3") (pintype "passive"))
      (node (ref "U7") (pin "3") (pinfunction "PA02_D1_3") (pintype "passive"))
    )
    (net (code "36") (name "/REGN") (class "Default")
      (node (ref "C19") (pin "1") (pinfunction "1_1") (pintype "passive"))
      (node (ref "LED2") (pin "1") (pinfunction "A_1") (pintype "passive"))
      (node (ref "R10") (pin "1") (pinfunction "1_1") (pintype "passive"))
      (node (ref "U1") (pin "2") (pinfunction "REGN_2") (pintype "passive"))
    )
    (net (code "37") (name "/RSRV1") (class "Default")
      (node (ref "R12") (pin "1") (pinfunction "1_1") (pintype "passive"))
      (node (ref "U3") (pin "22") (pinfunction "RESERVED_1_22") (pintype "passive"))
    )
    (net (code "38") (name "/RSRV2") (class "Default")
      (node (ref "R13") (pin "1") (pinfunction "1_1") (pintype "passive"))
      (node (ref "U3") (pin "23") (pinfunction "RESERVED_2_23") (pintype "passive"))
    )
    (net (code "39") (name "/RSRV3") (class "Default")
      (node (ref "R14") (pin "1") (pinfunction "1_1") (pintype "passive"))
      (node (ref "U3") (pin "30") (pinfunction "RESERVED_3_30") (pintype "passive"))
    )
    (net (code "40") (name "/SGND") (class "Default")
      (node (ref "C14") (pin "1") (pinfunction "1_1") (pintype "passive"))
      (node (ref "C15") (pin "1") (pinfunction "1_1") (pintype "passive"))
      (node (ref "CN1") (pin "1") (pinfunction "MH1_1") (pintype "passive"))
      (node (ref "CN1") (pin "2") (pinfunction "MH2_2") (pintype "passive"))
      (node (ref "CN1") (pin "3") (pinfunction "MH3_3") (pintype "passive"))
      (node (ref "CN1") (pin "4") (pinfunction "MH4_4") (pintype "passive"))
      (node (ref "R9") (pin "1") (pinfunction "1_1") (pintype "passive"))
    )
    (net (code "41") (name "/STAT") (class "Default")
      (node (ref "R26") (pin "2") (pinfunction "2_2") (pintype "passive"))
      (node (ref "U1") (pin "3") (pinfunction "STAT_3") (pintype "passive"))
    )
    (net (code "42") (name "/SW1") (class "Default")
      (node (ref "C38") (pin "2") (pinfunction "2_2") (pintype "passive"))
      (node (ref "L4") (pin "1") (pinfunction "1_1") (pintype "passive"))
      (node (ref "U6") (pin "8") (pinfunction "SW1_8") (pintype "passive"))
    )
    (net (code "43") (name "/SW2") (class "Default")
      (node (ref "C37") (pin "2") (pinfunction "2_2") (pintype "passive"))
      (node (ref "L4") (pin "2") (pinfunction "2_2") (pintype "passive"))
      (node (ref "U6") (pin "10") (pinfunction "SW2_10") (pintype "passive"))
    )
    (net (code "44") (name "/SWC") (class "Default")
      (node (ref "CN5") (pin "1") (pinfunction "1_1") (pintype "passive"))
      (node (ref "R39") (pin "2") (pinfunction "2_2") (pintype "passive"))
      (node (ref "U7") (pin "31") (pinfunction "PA30_31") (pintype "passive"))
    )
    (net (code "45") (name "/SWD") (class "Default")
      (node (ref "CN5") (pin "2") (pinfunction "2_2") (pintype "passive"))
      (node (ref "U7") (pin "32") (pinfunction "PA31_32") (pintype "passive"))
    )
    (net (code "46") (name "/VBUS") (class "Default")
      (node (ref "C7") (pin "1") (pinfunction "1_1") (pintype "passive"))
      (node (ref "C8") (pin "1") (pinfunction "1_1") (pintype "passive"))
      (node (ref "C9") (pin "1") (pinfunction "1_1") (pintype "passive"))
      (node (ref "F1") (pin "2") (pinfunction "2_2") (pintype "passive"))
      (node (ref "Q1") (pin "2") (pinfunction "TR1_SOURCE_1_2") (pintype "passive"))
      (node (ref "Q1") (pin "3") (pinfunction "TR1_SOURCE_2_3") (pintype "passive"))
      (node (ref "Q1") (pin "4") (pinfunction "TR1_SOURCE_3_4") (pintype "passive"))
      (node (ref "U3") (pin "26") (pinfunction "VBUS_1_26") (pintype "passive"))
      (node (ref "U3") (pin "27") (pinfunction "VBUS_2_27") (pintype "passive"))
    )
    (net (code "47") (name "/VDDA_M") (class "Default")
      (node (ref "C59") (pin "1") (pinfunction "1_1") (pintype "passive"))
      (node (ref "C60") (pin "1") (pinfunction "1_1") (pintype "passive"))
      (node (ref "FB1") (pin "2") (pinfunction "2_2") (pintype "passive"))
      (node (ref "U7") (pin "9") (pinfunction "VDDANA_9") (pintype "passive"))
    )
    (net (code "48") (name "/VIN") (class "Default")
      (node (ref "CN1") (pin "A9") (pinfunction "VBUS_A9") (pintype "passive"))
      (node (ref "CN1") (pin "B9") (pinfunction "VBUS_B9") (pintype "passive"))
      (node (ref "D3") (pin "4") (pinfunction "IN_1_4") (pintype "passive"))
      (node (ref "D3") (pin "5") (pinfunction "IN_2_5") (pintype "passive"))
      (node (ref "D3") (pin "6") (pinfunction "IN_3_6") (pintype "passive"))
      (node (ref "F1") (pin "1") (pinfunction "1_1") (pintype "passive"))
    )
    (net (code "49") (name "/VIN_GATE") (class "Default")
      (node (ref "D2") (pin "1") (pinfunction "K_1_1") (pintype "passive"))
      (node (ref "D2") (pin "3") (pinfunction "K_2_3") (pintype "passive"))
      (node (ref "Q2") (pin "4") (pinfunction "G_4") (pintype "passive"))
      (node (ref "R1") (pin "1") (pinfunction "1_1") (pintype "passive"))
    )
    (net (code "50") (name "AGND") (class "Default")
      (node (ref "C36") (pin "1") (pinfunction "1_1") (pintype "passive"))
      (node (ref "C40") (pin "2") (pinfunction "2_2") (pintype "passive"))
      (node (ref "C43") (pin "2") (pinfunction "2_2") (pintype "passive"))
      (node (ref "NT1") (pin "2") (pintype "passive"))
      (node (ref "R35") (pin "2") (pinfunction "2_2") (pintype "passive"))
      (node (ref "R37") (pin "1") (pinfunction "1_1") (pintype "passive"))
      (node (ref "R43") (pin "2") (pinfunction "2_2") (pintype "passive"))
      (node (ref "U6") (pin "17") (pinfunction "AGND_17") (pintype "passive"))
      (node (ref "U6") (pin "2") (pinfunction "MODE_2") (pintype "passive"))
      (node (ref "U6") (pin "5") (pinfunction "DITH/SYNC_5") (pintype "passive"))
    )
    (net (code "51") (name "GND") (class "Default")
      (node (ref "C10") (pin "2") (pinfunction "2_2") (pintype "passive"))
      (node (ref "C11") (pin "2") (pinfunction "2_2") (pintype "passive"))
      (node (ref "C12") (pin "2") (pinfunction "2_2") (pintype "passive"))
      (node (ref "C13") (pin "2") (pinfunction "2_2") (pintype "passive"))
      (node (ref "C14") (pin "2") (pinfunction "2_2") (pintype "passive"))
      (node (ref "C15") (pin "2") (pinfunction "2_2") (pintype "passive"))
      (node (ref "C16") (pin "2") (pinfunction "2_2") (pintype "passive"))
      (node (ref "C17") (pin "2") (pinfunction "2_2") (pintype "passive"))
      (node (ref "C18") (pin "2") (pinfunction "2_2") (pintype "passive"))
      (node (ref "C19") (pin "2") (pinfunction "2_2") (pintype "passive"))
      (node (ref "C2") (pin "2") (pinfunction "2_2") (pintype "passive"))
      (node (ref "C20") (pin "2") (pinfunction "2_2") (pintype "passive"))
      (node (ref "C21") (pin "2") (pinfunction "2_2") (pintype "passive"))
      (node (ref "C22") (pin "2") (pinfunction "2_2") (pintype "passive"))
      (node (ref "C23") (pin "2") (pinfunction "2_2") (pintype "passive"))
      (node (ref "C24") (pin "2") (pinfunction "2_2") (pintype "passive"))
      (node (ref "C25") (pin "2") (pinfunction "2_2") (pintype "passive"))
      (node (ref "C26") (pin "2") (pinfunction "2_2") (pintype "passive"))
      (node (ref "C27") (pin "2") (pinfunction "2_2") (pintype "passive"))
      (node (ref "C28") (pin "2") (pinfunction "2_2") (pintype "passive"))
      (node (ref "C29") (pin "2") (pinfunction "2_2") (pintype "passive"))
      (node (ref "C3") (pin "2") (pinfunction "2_2") (pintype "passive"))
      (node (ref "C30") (pin "2") (pinfunction "2_2") (pintype "passive"))
      (node (ref "C31") (pin "2") (pinfunction "2_2") (pintype "passive"))
      (node (ref "C32") (pin "2") (pinfunction "2_2") (pintype "passive"))
      (node (ref "C33") (pin "2") (pinfunction "2_2") (pintype "passive"))
      (node (ref "C34") (pin "2") (pinfunction "2_2") (pintype "passive"))
      (node (ref "C35") (pin "2") (pinfunction "2_2") (pintype "passive"))
      (node (ref "C39") (pin "2") (pinfunction "2_2") (pintype "passive"))
      (node (ref "C4") (pin "2") (pinfunction "2_2") (pintype "passive"))
      (node (ref "C41") (pin "2") (pinfunction "2_2") (pintype "passive"))
      (node (ref "C44") (pin "2") (pinfunction "2_2") (pintype "passive"))
      (node (ref "C45") (pin "2") (pinfunction "2_2") (pintype "passive"))
      (node (ref "C46") (pin "2") (pinfunction "2_2") (pintype "passive"))
      (node (ref "C47") (pin "2") (pinfunction "2_2") (pintype "passive"))
      (node (ref "C48") (pin "2") (pinfunction "2_2") (pintype "passive"))
      (node (ref "C49") (pin "2") (pinfunction "2_2") (pintype "passive"))
      (node (ref "C5") (pin "2") (pinfunction "2_2") (pintype "passive"))
      (node (ref "C50") (pin "2") (pinfunction "2_2") (pintype "passive"))
      (node (ref "C51") (pin "2") (pinfunction "2_2") (pintype "passive"))
      (node (ref "C52") (pin "2") (pinfunction "2_2") (pintype "passive"))
      (node (ref "C53") (pin "2") (pinfunction "-_2") (pintype "passive"))
      (node (ref "C54") (pin "2") (pinfunction "2_2") (pintype "passive"))
      (node (ref "C55") (pin "2") (pinfunction "2_2") (pintype "passive"))
      (node (ref "C56") (pin "2") (pinfunction "2_2") (pintype "passive"))
      (node (ref "C57") (pin "2") (pinfunction "2_2") (pintype "passive"))
      (node (ref "C58") (pin "2") (pinfunction "2_2") (pintype "passive"))
      (node (ref "C59") (pin "2") (pinfunction "2_2") (pintype "passive"))
      (node (ref "C6") (pin "2") (pinfunction "2_2") (pintype "passive"))
      (node (ref "C60") (pin "2") (pinfunction "2_2") (pintype "passive"))
      (node (ref "C61") (pin "2") (pinfunction "2_2") (pintype "passive"))
      (node (ref "C7") (pin "2") (pinfunction "2_2") (pintype "passive"))
      (node (ref "C8") (pin "2") (pinfunction "2_2") (pintype "passive"))
      (node (ref "C9") (pin "2") (pinfunction "2_2") (pintype "passive"))
      (node (ref "CN1") (pin "A12") (pinfunction "GND_A12") (pintype "passive"))
      (node (ref "CN1") (pin "B12") (pinfunction "GND_B12") (pintype "passive"))
      (node (ref "CN2") (pin "2") (pinfunction "GND_2") (pintype "power_in"))
      (node (ref "CN3") (pin "2") (pinfunction "2_2") (pintype "passive"))
      (node (ref "CN3") (pin "3") (pinfunction "MNT_1_3") (pintype "passive"))
      (node (ref "CN3") (pin "4") (pinfunction "MNT_2_4") (pintype "passive"))
      (node (ref "CN4") (pin "3") (pinfunction "3_3") (pintype "passive"))
      (node (ref "CN4") (pin "5") (pinfunction "MNT_1_5") (pintype "passive"))
      (node (ref "CN4") (pin "6") (pinfunction "MNT_2_6") (pintype "passive"))
      (node (ref "CN5") (pin "4") (pinfunction "4_4") (pintype "passive"))
      (node (ref "CN5") (pin "5") (pinfunction "MNT_1_5") (pintype "passive"))
      (node (ref "CN5") (pin "6") (pinfunction "MNT_2_6") (pintype "passive"))
      (node (ref "D3") (pin "1") (pinfunction "GND_1_1") (pintype "passive"))
      (node (ref "D3") (pin "2") (pinfunction "GND_2_2") (pintype "passive"))
      (node (ref "D3") (pin "3") (pinfunction "GND_3_3") (pintype "passive"))
      (node (ref "D3") (pin "7") (pinfunction "EP_7") (pintype "passive"))
      (node (ref "LED3") (pin "6") (pinfunction "GND_6") (pintype "passive"))
      (node (ref "LED3") (pin "8") (pinfunction "GND_8") (pintype "passive"))
      (node (ref "LED4") (pin "2") (pinfunction "K_2") (pintype "passive"))
      (node (ref "NT1") (pin "1") (pintype "passive"))
      (node (ref "Q3") (pin "2") (pinfunction "E_2") (pintype "passive"))
      (node (ref "Q4") (pin "3") (pinfunction "S_3") (pintype "passive"))
      (node (ref "Q4") (pin "4") (pinfunction "S_4") (pintype "passive"))
      (node (ref "Q5") (pin "3") (pinfunction "S_3") (pintype "passive"))
      (node (ref "Q5") (pin "4") (pinfunction "S_4") (pintype "passive"))
      (node (ref "Q6") (pin "3") (pinfunction "S_3") (pintype "passive"))
      (node (ref "Q6") (pin "4") (pinfunction "S_4") (pintype "passive"))
      (node (ref "R1") (pin "2") (pinfunction "2_2") (pintype "passive"))
      (node (ref "R12") (pin "2") (pinfunction "2_2") (pintype "passive"))
      (node (ref "R13") (pin "2") (pinfunction "2_2") (pintype "passive"))
      (node (ref "R14") (pin "2") (pinfunction "2_2") (pintype "passive"))
      (node (ref "R15") (pin "2") (pinfunction "2_2") (pintype "passive"))
      (node (ref "R16") (pin "2") (pinfunction "2_2") (pintype "passive"))
      (node (ref "R17") (pin "2") (pinfunction "2_2") (pintype "passive"))
      (node (ref "R18") (pin "2") (pinfunction "2_2") (pintype "passive"))
      (node (ref "R19") (pin "2") (pinfunction "2_2") (pintype "passive"))
      (node (ref "R2") (pin "2") (pinfunction "2_2") (pintype "passive"))
      (node (ref "R20") (pin "2") (pinfunction "2_2") (pintype "passive"))
      (node (ref "R27") (pin "1") (pinfunction "1_1") (pintype "passive"))
      (node (ref "R29") (pin "2") (pinfunction "2_2") (pintype "passive"))
      (node (ref "R3") (pin "2") (pinfunction "2_2") (pintype "passive"))
      (node (ref "R30") (pin "2") (pinfunction "2_2") (pintype "passive"))
      (node (ref "R31") (pin "2") (pinfunction "2_2") (pintype "passive"))
      (node (ref "R32") (pin "2") (pinfunction "2_2") (pintype "passive"))
      (node (ref "R9") (pin "2") (pinfunction "2_2") (pintype "passive"))
      (node (ref "SW1") (pin "2") (pinfunction "2_2") (pintype "passive"))
      (node (ref "SW1") (pin "4") (pinfunction "4_4") (pintype "passive"))
      (node (ref "SW2") (pin "3") (pinfunction "NC_3") (pintype "power_in"))
      (node (ref "SW2") (pin "4") (pinfunction "4_4") (pintype "power_in"))
      (node (ref "SW3") (pin "1") (pinfunction "1_1") (pintype "passive"))
      (node (ref "TP4") (pin "1") (pinfunction "1_1") (pintype "passive"))
      (node (ref "TP5") (pin "1") (pinfunction "1_1") (pintype "passive"))
      (node (ref "U1") (pin "11") (pinfunction "GND_1_11") (pintype "passive"))
      (node (ref "U1") (pin "12") (pinfunction "GND_2_12") (pintype "passive"))
      (node (ref "U1") (pin "17") (pinfunction "EP_17") (pintype "passive"))
      (node (ref "U1") (pin "6") (pinfunction "~{EN}_6") (pintype "passive"))
      (node (ref "U10") (pin "10") (pinfunction "0P4V_10") (pintype "passive"))
      (node (ref "U10") (pin "11") (pinfunction "0P2V_11") (pintype "passive"))
      (node (ref "U10") (pin "12") (pinfunction "0P1V_12") (pintype "passive"))
      (node (ref "U10") (pin "21") (pinfunction "GND_2_21") (pintype "passive"))
      (node (ref "U10") (pin "7") (pinfunction "GND_1_7") (pintype "passive"))
      (node (ref "U10") (pin "8") (pinfunction "1P6V_8") (pintype "passive"))
      (node (ref "U10") (pin "9") (pinfunction "0P8V_9") (pintype "passive"))
      (node (ref "U2") (pin "2") (pinfunction "VSS_2") (pintype "passive"))
      (node (ref "U3") (pin "11") (pinfunction "GND_1_11") (pintype "passive"))
      (node (ref "U3") (pin "12") (pinfunction "GND_2_12") (pintype "passive"))
      (node (ref "U3") (pin "14") (pinfunction "GND_3_14") (pintype "passive"))
      (node (ref "U3") (pin "15") (pinfunction "GND_4_15") (pintype "passive"))
      (node (ref "U3") (pin "16") (pinfunction "GND_5_16") (pintype "passive"))
      (node (ref "U3") (pin "28") (pinfunction "GND_6_28") (pintype "passive"))
      (node (ref "U3") (pin "29") (pinfunction "GND_7_29") (pintype "passive"))
      (node (ref "U3") (pin "33") (pinfunction "GND_8_33") (pintype "passive"))
      (node (ref "U3") (pin "8") (pinfunction "I2CT_SDA_8") (pintype "passive"))
      (node (ref "U3") (pin "9") (pinfunction "I2CT_SCL_9") (pintype "passive"))
      (node (ref "U4") (pin "11") (pinfunction "EP_11") (pintype "passive"))
      (node (ref "U4") (pin "4") (pinfunction "PS/SYNC_4") (pintype "passive"))
      (node (ref "U4") (pin "7") (pinfunction "GND_7") (pintype "passive"))
      (node (ref "U5") (pin "3") (pinfunction "GND_3") (pintype "power_in"))
      (node (ref "U5") (pin "7") (pinfunction "EP_7") (pintype "power_in"))
      (node (ref "U6") (pin "22") (pinfunction "PGND_2_22") (pintype "passive"))
      (node (ref "U6") (pin "23") (pinfunction "PGND_3_23") (pintype "passive"))
      (node (ref "U6") (pin "9") (pinfunction "PGND_1_9") (pintype "passive"))
      (node (ref "U7") (pin "10") (pinfunction "GND_1_10") (pintype "passive"))
      (node (ref "U7") (pin "28") (pinfunction "GND_2_28") (pintype "passive"))
      (node (ref "U7") (pin "33") (pinfunction "EP_33") (pintype "passive"))
      (node (ref "U8") (pin "3") (pinfunction "GND_3") (pintype "power_in"))
      (node (ref "U8") (pin "7") (pinfunction "Thermal_Pad_7") (pintype "power_in"))
      (node (ref "U9") (pin "2") (pinfunction "VSS_2") (pintype "passive"))
    )
    (net (code "52") (name "LDO_1V5") (class "Default")
      (node (ref "C18") (pin "1") (pinfunction "1_1") (pintype "passive"))
      (node (ref "U3") (pin "4") (pinfunction "LDO_1V5_4") (pintype "passive"))
    )
    (net (code "53") (name "LDO_3V3") (class "Default")
      (node (ref "C17") (pin "1") (pinfunction "1_1") (pintype "passive"))
      (node (ref "R4") (pin "1") (pinfunction "1_1") (pintype "passive"))
      (node (ref "R5") (pin "1") (pinfunction "1_1") (pintype "passive"))
      (node (ref "R6") (pin "1") (pinfunction "1_1") (pintype "passive"))
      (node (ref "R7") (pin "1") (pinfunction "1_1") (pintype "passive"))
      (node (ref "R8") (pin "1") (pinfunction "1_1") (pintype "passive"))
      (node (ref "U3") (pin "1") (pinfunction "LDO_3V3_1") (pintype "passive"))
    )
    (net (code "54") (name "Net-(C40-Pad1)") (class "Default")
      (node (ref "C40") (pin "1") (pinfunction "1_1") (pintype "passive"))
      (node (ref "R36") (pin "2") (pinfunction "2_2") (pintype "passive"))
    )
    (net (code "55") (name "Net-(LED1-K)") (class "Default")
      (node (ref "LED1") (pin "2") (pinfunction "K_2") (pintype "passive"))
      (node (ref "R21") (pin "1") (pinfunction "1_1") (pintype "passive"))
    )
    (net (code "56") (name "Net-(LED2-K)") (class "Default")
      (node (ref "LED2") (pin "2") (pinfunction "K_2") (pintype "passive"))
      (node (ref "R26") (pin "1") (pinfunction "1_1") (pintype "passive"))
    )
    (net (code "57") (name "Net-(LED3-VDD-Pad1)") (class "Default")
      (node (ref "LED3") (pin "1") (pinfunction "VDD_1") (pintype "passive"))
      (node (ref "LED3") (pin "7") (pinfunction "VDD_7") (pintype "passive"))
      (node (ref "R44") (pin "2") (pinfunction "2_2") (pintype "passive"))
    )
    (net (code "58") (name "Net-(LED4-A)") (class "Default")
      (node (ref "LED4") (pin "1") (pinfunction "A_1") (pintype "passive"))
      (node (ref "R46") (pin "2") (pinfunction "2_2") (pintype "passive"))
    )
    (net (code "59") (name "Net-(Q3-B)") (class "Default")
      (node (ref "Q3") (pin "1") (pinfunction "B_1") (pintype "passive"))
      (node (ref "R28") (pin "2") (pinfunction "2_2") (pintype "passive"))
    )
    (net (code "60") (name "Net-(Q4-D)") (class "Default")
      (node (ref "Q4") (pin "1") (pinfunction "D_1") (pintype "passive"))
      (node (ref "Q6") (pin "1") (pinfunction "D_1") (pintype "passive"))
      (node (ref "R24") (pin "2") (pinfunction "2_2") (pintype "passive"))
      (node (ref "U5") (pin "5") (pinfunction "CTRL_5") (pintype "input"))
    )
    (net (code "61") (name "Net-(Q5-D)") (class "Default")
      (node (ref "Q5") (pin "1") (pinfunction "D_1") (pintype "passive"))
      (node (ref "Q6") (pin "2") (pinfunction "G_2") (pintype "passive"))
      (node (ref "R23") (pin "2") (pinfunction "2_2") (pintype "passive"))
    )
    (net (code "62") (name "Net-(R22-Pad2)") (class "Default")
      (node (ref "R22") (pin "2") (pinfunction "2_2") (pintype "passive"))
      (node (ref "SW2") (pin "1") (pinfunction "1_1") (pintype "power_in"))
    )
    (net (code "63") (name "Net-(R30-Pad1)") (class "Default")
      (node (ref "R30") (pin "1") (pinfunction "1_1") (pintype "passive"))
      (node (ref "SW2") (pin "2") (pinfunction "2_2") (pintype "passive"))
    )
    (net (code "64") (name "Net-(R42-Pad2)") (class "Default")
      (node (ref "R42") (pin "2") (pinfunction "2_2") (pintype "passive"))
      (node (ref "SW3") (pin "2") (pinfunction "2_2") (pintype "passive"))
    )
    (net (code "65") (name "Net-(U1-BTST)") (class "Default")
      (node (ref "C1") (pin "1") (pinfunction "1_1") (pintype "passive"))
      (node (ref "U1") (pin "15") (pinfunction "BTST_15") (pintype "passive"))
    )
    (net (code "66") (name "Net-(U1-ICHG)") (class "Default")
      (node (ref "R2") (pin "1") (pinfunction "1_1") (pintype "passive"))
      (node (ref "U1") (pin "4") (pinfunction "ICHG_4") (pintype "passive"))
    )
    (net (code "67") (name "Net-(U1-PMID)") (class "Default")
      (node (ref "C6") (pin "1") (pinfunction "1_1") (pintype "passive"))
      (node (ref "U1") (pin "16") (pinfunction "PMID_16") (pintype "passive"))
    )
    (net (code "68") (name "Net-(U1-SW_1)") (class "Default")
      (node (ref "C1") (pin "2") (pinfunction "2_2") (pintype "passive"))
      (node (ref "L1") (pin "1") (pinfunction "1_1") (pintype "passive"))
      (node (ref "U1") (pin "13") (pinfunction "SW_1_13") (pintype "passive"))
      (node (ref "U1") (pin "14") (pinfunction "SW_2_14") (pintype "passive"))
    )
    (net (code "69") (name "Net-(U1-VSET)") (class "Default")
      (node (ref "R3") (pin "1") (pinfunction "1_1") (pintype "passive"))
      (node (ref "U1") (pin "9") (pinfunction "VSET_9") (pintype "passive"))
    )
    (net (code "70") (name "Net-(U4-FB)") (class "Default")
      (node (ref "C30") (pin "1") (pinfunction "1_1") (pintype "passive"))
      (node (ref "R25") (pin "2") (pinfunction "2_2") (pintype "passive"))
      (node (ref "R29") (pin "1") (pinfunction "1_1") (pintype "passive"))
      (node (ref "U4") (pin "8") (pinfunction "FB_8") (pintype "passive"))
    )
    (net (code "71") (name "Net-(U4-L1)") (class "Default")
      (node (ref "L2") (pin "1") (pinfunction "1_1") (pintype "passive"))
      (node (ref "U4") (pin "1") (pinfunction "L1_1") (pintype "passive"))
    )
    (net (code "72") (name "Net-(U4-L2)") (class "Default")
      (node (ref "L2") (pin "2") (pinfunction "2_2") (pintype "passive"))
      (node (ref "U4") (pin "10") (pinfunction "L2_10") (pintype "passive"))
    )
    (net (code "73") (name "Net-(U4-VAUX)") (class "Default")
      (node (ref "C29") (pin "1") (pinfunction "1_1") (pintype "passive"))
      (node (ref "U4") (pin "6") (pinfunction "VAUX_6") (pintype "passive"))
    )
    (net (code "74") (name "Net-(U5-COMP)") (class "Default")
      (node (ref "C32") (pin "1") (pinfunction "1_1") (pintype "passive"))
      (node (ref "U5") (pin "2") (pinfunction "COMP_2") (pintype "passive"))
    )
    (net (code "75") (name "Net-(U5-SW)") (class "Default")
      (node (ref "D4") (pin "2") (pinfunction "2_2") (pintype "passive"))
      (node (ref "L3") (pin "2") (pinfunction "2_2") (pintype "passive"))
      (node (ref "U5") (pin "4") (pinfunction "SW_4") (pintype "power_in"))
    )
    (net (code "76") (name "Net-(U6-BOOT1)") (class "Default")
      (node (ref "C38") (pin "1") (pinfunction "1_1") (pintype "passive"))
      (node (ref "U6") (pin "20") (pinfunction "BOOT1_20") (pintype "passive"))
    )
    (net (code "77") (name "Net-(U6-BOOT2)") (class "Default")
      (node (ref "C37") (pin "1") (pinfunction "1_1") (pintype "passive"))
      (node (ref "U6") (pin "19") (pinfunction "BOOT2_19") (pintype "passive"))
    )
    (net (code "78") (name "Net-(U6-CDC)") (class "Default")
      (node (ref "R35") (pin "1") (pinfunction "1_1") (pintype "passive"))
      (node (ref "U6") (pin "16") (pinfunction "CDC_16") (pintype "passive"))
    )
    (net (code "79") (name "Net-(U6-COMP)") (class "Default")
      (node (ref "C36") (pin "2") (pinfunction "2_2") (pintype "passive"))
      (node (ref "R36") (pin "1") (pinfunction "1_1") (pintype "passive"))
      (node (ref "U6") (pin "15") (pinfunction "COMP_15") (pintype "passive"))
    )
    (net (code "80") (name "Net-(U6-EXTVCC)") (class "Default")
      (node (ref "C39") (pin "1") (pinfunction "1_1") (pintype "passive"))
      (node (ref "C43") (pin "1") (pinfunction "1_1") (pintype "passive"))
      (node (ref "U6") (pin "18") (pinfunction "VCC_18") (pintype "passive"))
      (node (ref "U6") (pin "21") (pinfunction "EXTVCC_21") (pintype "passive"))
    )
    (net (code "81") (name "Net-(U6-FB)") (class "Default")
      (node (ref "R34") (pin "2") (pinfunction "2_2") (pintype "passive"))
      (node (ref "R37") (pin "2") (pinfunction "2_2") (pintype "passive"))
      (node (ref "U6") (pin "14") (pinfunction "FB_14") (pintype "passive"))
    )
    (net (code "82") (name "Net-(U6-FSW)") (class "Default")
      (node (ref "R43") (pin "1") (pinfunction "1_1") (pintype "passive"))
      (node (ref "U6") (pin "6") (pinfunction "FSW_6") (pintype "passive"))
    )
    (net (code "83") (name "Net-(U7-PA10)") (class "Default")
      (node (ref "R46") (pin "1") (pinfunction "1_1") (pintype "passive"))
      (node (ref "U7") (pin "13") (pinfunction "PA10_13") (pintype "passive"))
    )
    (net (code "84") (name "Net-(U7-VDDCORE)") (class "Default")
      (node (ref "C41") (pin "1") (pinfunction "1_1") (pintype "passive"))
      (node (ref "U7") (pin "29") (pinfunction "VDDCORE_29") (pintype "passive"))
    )
    (net (code "85") (name "Net-(U7-~{RESET})") (class "Default")
      (node (ref "C50") (pin "1") (pinfunction "1_1") (pintype "passive"))
      (node (ref "R42") (pin "1") (pinfunction "1_1") (pintype "passive"))
      (node (ref "U7") (pin "26") (pinfunction "~{RESET}_26") (pintype "passive"))
    )
    (net (code "86") (name "Net-(U10-NR)") (class "Default")
      (node (ref "C54") (pin "1") (pinfunction "1_1") (pintype "passive"))
      (node (ref "U10") (pin "14") (pinfunction "NR_14") (pintype "passive"))
    )
    (net (code "87") (name "VBAT") (class "Default")
      (node (ref "C21") (pin "1") (pinfunction "1_1") (pintype "passive"))
      (node (ref "C3") (pin "1") (pinfunction "1_1") (pintype "passive"))
      (node (ref "C61") (pin "1") (pinfunction "1_1") (pintype "passive"))
      (node (ref "CN2") (pin "1") (pinfunction "VBAT_1") (pintype "power_in"))
      (node (ref "L1") (pin "2") (pinfunction "2_2") (pintype "passive"))
      (node (ref "Q2") (pin "5") (pinfunction "D_1_5") (pintype "passive"))
      (node (ref "Q2") (pin "6") (pinfunction "D_2_6") (pintype "passive"))
      (node (ref "Q2") (pin "7") (pinfunction "D_3_7") (pintype "passive"))
      (node (ref "Q2") (pin "8") (pinfunction "D_4_8") (pintype "passive"))
      (node (ref "R11") (pin "1") (pinfunction "1_1") (pintype "passive"))
      (node (ref "TP2") (pin "1") (pinfunction "1_1") (pintype "passive"))
      (node (ref "TP3") (pin "1") (pinfunction "1_1") (pintype "passive"))
      (node (ref "U1") (pin "10") (pinfunction "BAT_10") (pintype "passive"))
      (node (ref "U2") (pin "4") (pinfunction "VIN_4") (pintype "passive"))
      (node (ref "U9") (pin "1") (pinfunction "VIN_1") (pintype "passive"))
      (node (ref "U9") (pin "3") (pinfunction "CE_3") (pintype "passive"))
    )
    (net (code "88") (name "VIN_3V3") (class "Default")
      (node (ref "C16") (pin "1") (pinfunction "1_1") (pintype "passive"))
      (node (ref "U3") (pin "32") (pinfunction "VIN_3V3_32") (pintype "passive"))
    )
    (net (code "89") (name "VOUT") (class "Default")
      (node (ref "C45") (pin "1") (pinfunction "1_1") (pintype "passive"))
      (node (ref "C46") (pin "1") (pinfunction "1_1") (pintype "passive"))
      (node (ref "C47") (pin "1") (pinfunction "1_1") (pintype "passive"))
      (node (ref "R40") (pin "2") (pinfunction "2_2") (pintype "passive"))
      (node (ref "R41") (pin "2") (pinfunction "2_2") (pintype "passive"))
      (node (ref "U6") (pin "11") (pinfunction "VOUT_11") (pintype "passive"))
    )
    (net (code "90") (name "VSYS") (class "Default")
      (node (ref "C24") (pin "1") (pinfunction "1_1") (pintype "passive"))
      (node (ref "C25") (pin "1") (pinfunction "1_1") (pintype "passive"))
      (node (ref "C33") (pin "1") (pinfunction "1_1") (pintype "passive"))
      (node (ref "C34") (pin "1") (pinfunction "1_1") (pintype "passive"))
      (node (ref "C35") (pin "1") (pinfunction "1_1") (pintype "passive"))
      (node (ref "C4") (pin "1") (pinfunction "1_1") (pintype "passive"))
      (node (ref "C5") (pin "1") (pinfunction "1_1") (pintype "passive"))
      (node (ref "D1") (pin "3") (pinfunction "K_3") (pintype "passive"))
      (node (ref "Q2") (pin "1") (pinfunction "S_1_1") (pintype "passive"))
      (node (ref "Q2") (pin "2") (pinfunction "S_2_2") (pintype "passive"))
      (node (ref "Q2") (pin "3") (pinfunction "S_3_3") (pintype "passive"))
      (node (ref "TP1") (pin "1") (pinfunction "1_1") (pintype "passive"))
      (node (ref "U4") (pin "2") (pinfunction "VIN_2") (pintype "passive"))
      (node (ref "U6") (pin "7") (pinfunction "VIN_7") (pintype "passive"))
    )
    (net (code "91") (name "unconnected-(CN2-NC-Pad4)") (class "Default")
      (node (ref "CN2") (pin "4") (pinfunction "NC_4") (pintype "power_in+no_connect"))
    )
    (net (code "92") (name "unconnected-(CN2-NTC-Pad3)") (class "Default")
      (node (ref "CN2") (pin "3") (pinfunction "NTC_3") (pintype "output+no_connect"))
    )
    (net (code "93") (name "unconnected-(LED3-CK0-Pad2)") (class "Default")
      (node (ref "LED3") (pin "2") (pinfunction "CK0_2") (pintype "passive+no_connect"))
    )
    (net (code "94") (name "unconnected-(LED3-SD0-Pad3)") (class "Default")
      (node (ref "LED3") (pin "3") (pinfunction "SD0_3") (pintype "passive+no_connect"))
    )
    (net (code "95") (name "unconnected-(Q1-TR1_DRAIN{slash}TR2_DRAIN-Pad9)") (class "Default")
      (node (ref "Q1") (pin "9") (pinfunction "TR1_DRAIN/TR2_DRAIN_9") (pintype "passive+no_connect"))
    )
    (net (code "96") (name "unconnected-(U1-NC-Pad8)") (class "Default")
      (node (ref "U1") (pin "8") (pinfunction "NC_8") (pintype "passive+no_connect"))
    )
    (net (code "97") (name "unconnected-(U1-POL-Pad5)") (class "Default")
      (node (ref "U1") (pin "5") (pinfunction "POL_5") (pintype "passive+no_connect"))
    )
    (net (code "98") (name "unconnected-(U2-NC-Pad1)") (class "Default")
      (node (ref "U2") (pin "1") (pinfunction "NC_1") (pintype "passive+no_connect"))
    )
    (net (code "99") (name "unconnected-(U3-CAP_MIS-Pad6)") (class "Default")
      (node (ref "U3") (pin "6") (pinfunction "CAP_MIS_6") (pintype "passive+no_connect"))
    )
    (net (code "100") (name "unconnected-(U3-DBG_ACC-Pad10)") (class "Default")
      (node (ref "U3") (pin "10") (pinfunction "DBG_ACC_10") (pintype "passive+no_connect"))
    )
    (net (code "101") (name "unconnected-(U3-PLUG_EVENT-Pad31)") (class "Default")
      (node (ref "U3") (pin "31") (pinfunction "PLUG_EVENT_31") (pintype "passive+no_connect"))
    )
    (net (code "102") (name "unconnected-(U3-PLUG_FLIP-Pad13)") (class "Default")
      (node (ref "U3") (pin "13") (pinfunction "PLUG_FLIP_13") (pintype "passive+no_connect"))
    )
    (net (code "103") (name "unconnected-(U3-~{SINK_EN}-Pad18)") (class "Default")
      (node (ref "U3") (pin "18") (pinfunction "~{SINK_EN}_18") (pintype "passive+no_connect"))
    )
    (net (code "104") (name "unconnected-(U4-PG-Pad5)") (class "Default")
      (node (ref "U4") (pin "5") (pinfunction "PG_5") (pintype "passive+no_connect"))
    )
    (net (code "105") (name "unconnected-(U6-PG-Pad3)") (class "Default")
      (node (ref "U6") (pin "3") (pinfunction "PG_3") (pintype "passive+no_connect"))
    )
    (net (code "106") (name "unconnected-(U6-~{CC}-Pad4)") (class "Default")
      (node (ref "U6") (pin "4") (pinfunction "~{CC}_4") (pintype "passive+no_connect"))
    )
    (net (code "107") (name "unconnected-(U7-PA03-Pad4)") (class "Default")
      (node (ref "U7") (pin "4") (pinfunction "PA03_4") (pintype "passive+no_connect"))
    )
    (net (code "108") (name "unconnected-(U7-PA04-Pad5)") (class "Default")
      (node (ref "U7") (pin "5") (pinfunction "PA04_5") (pintype "passive+no_connect"))
    )
    (net (code "109") (name "unconnected-(U7-PA05-Pad6)") (class "Default")
      (node (ref "U7") (pin "6") (pinfunction "PA05_6") (pintype "passive+no_connect"))
    )
    (net (code "110") (name "unconnected-(U7-PA11-Pad14)") (class "Default")
      (node (ref "U7") (pin "14") (pinfunction "PA11_14") (pintype "passive+no_connect"))
    )
    (net (code "111") (name "unconnected-(U7-PA14-Pad15)") (class "Default")
      (node (ref "U7") (pin "15") (pinfunction "PA14_15") (pintype "passive+no_connect"))
    )
    (net (code "112") (name "unconnected-(U7-PA15-Pad16)") (class "Default")
      (node (ref "U7") (pin "16") (pinfunction "PA15_16") (pintype "passive+no_connect"))
    )
    (net (code "113") (name "unconnected-(U7-PA16-Pad17)") (class "Default")
      (node (ref "U7") (pin "17") (pinfunction "PA16_17") (pintype "passive+no_connect"))
    )
    (net (code "114") (name "unconnected-(U7-PA17-Pad18)") (class "Default")
      (node (ref "U7") (pin "18") (pinfunction "PA17_18") (pintype "passive+no_connect"))
    )
    (net (code "115") (name "unconnected-(U7-PA18-Pad19)") (class "Default")
      (node (ref "U7") (pin "19") (pinfunction "PA18_19") (pintype "passive+no_connect"))
    )
    (net (code "116") (name "unconnected-(U7-PA19-Pad20)") (class "Default")
      (node (ref "U7") (pin "20") (pinfunction "PA19_20") (pintype "passive+no_connect"))
    )
    (net (code "117") (name "unconnected-(U7-PA22-Pad21)") (class "Default")
      (node (ref "U7") (pin "21") (pinfunction "PA22_21") (pintype "passive+no_connect"))
    )
    (net (code "118") (name "unconnected-(U7-PA23-Pad22)") (class "Default")
      (node (ref "U7") (pin "22") (pinfunction "PA23_22") (pintype "passive+no_connect"))
    )
    (net (code "119") (name "unconnected-(U7-PA27-Pad25)") (class "Default")
      (node (ref "U7") (pin "25") (pinfunction "PA27_25") (pintype "passive+no_connect"))
    )
    (net (code "120") (name "unconnected-(U7-PA28-Pad27)") (class "Default")
      (node (ref "U7") (pin "27") (pinfunction "PA28_27") (pintype "passive+no_connect"))
    )
    (net (code "121") (name "unconnected-(U8-NC-Pad2)") (class "Default")
      (node (ref "U8") (pin "2") (pinfunction "NC_2") (pintype "passive+no_connect"))
    )
    (net (code "122") (name "unconnected-(U8-NC-Pad5)") (class "Default")
      (node (ref "U8") (pin "5") (pinfunction "NC_5") (pintype "passive+no_connect"))
    )
    (net (code "123") (name "unconnected-(U9-NC-Pad4)") (class "Default")
      (node (ref "U9") (pin "4") (pinfunction "NC_4") (pintype "passive+no_connect"))
    )
    (net (code "124") (name "unconnected-(U10-3P2V-Pad6)") (class "Default")
      (node (ref "U10") (pin "6") (pinfunction "3P2V_6") (pintype "passive+no_connect"))
    )
    (net (code "125") (name "unconnected-(U10-6P4V1-Pad5)") (class "Default")
      (node (ref "U10") (pin "5") (pinfunction "6P4V1_5") (pintype "passive+no_connect"))
    )
    (net (code "126") (name "unconnected-(U10-6P4V2-Pad4)") (class "Default")
      (node (ref "U10") (pin "4") (pinfunction "6P4V2_4") (pintype "passive+no_connect"))
    )
    (net (code "127") (name "unconnected-(U10-NC_1-Pad2)") (class "Default")
      (node (ref "U10") (pin "2") (pinfunction "NC_1_2") (pintype "passive+no_connect"))
    )
    (net (code "128") (name "unconnected-(U10-NC_2-Pad17)") (class "Default")
      (node (ref "U10") (pin "17") (pinfunction "NC_2_17") (pintype "passive+no_connect"))
    )
    (net (code "129") (name "unconnected-(U10-NC_3-Pad18)") (class "Default")
      (node (ref "U10") (pin "18") (pinfunction "NC_3_18") (pintype "passive+no_connect"))
    )
    (net (code "130") (name "unconnected-(U10-NC_4-Pad19)") (class "Default")
      (node (ref "U10") (pin "19") (pinfunction "NC_4_19") (pintype "passive+no_connect"))
    )
  )
)
